# stm32f767igt6.net
KiCad netlist of a schematic drawn in Altium Designer
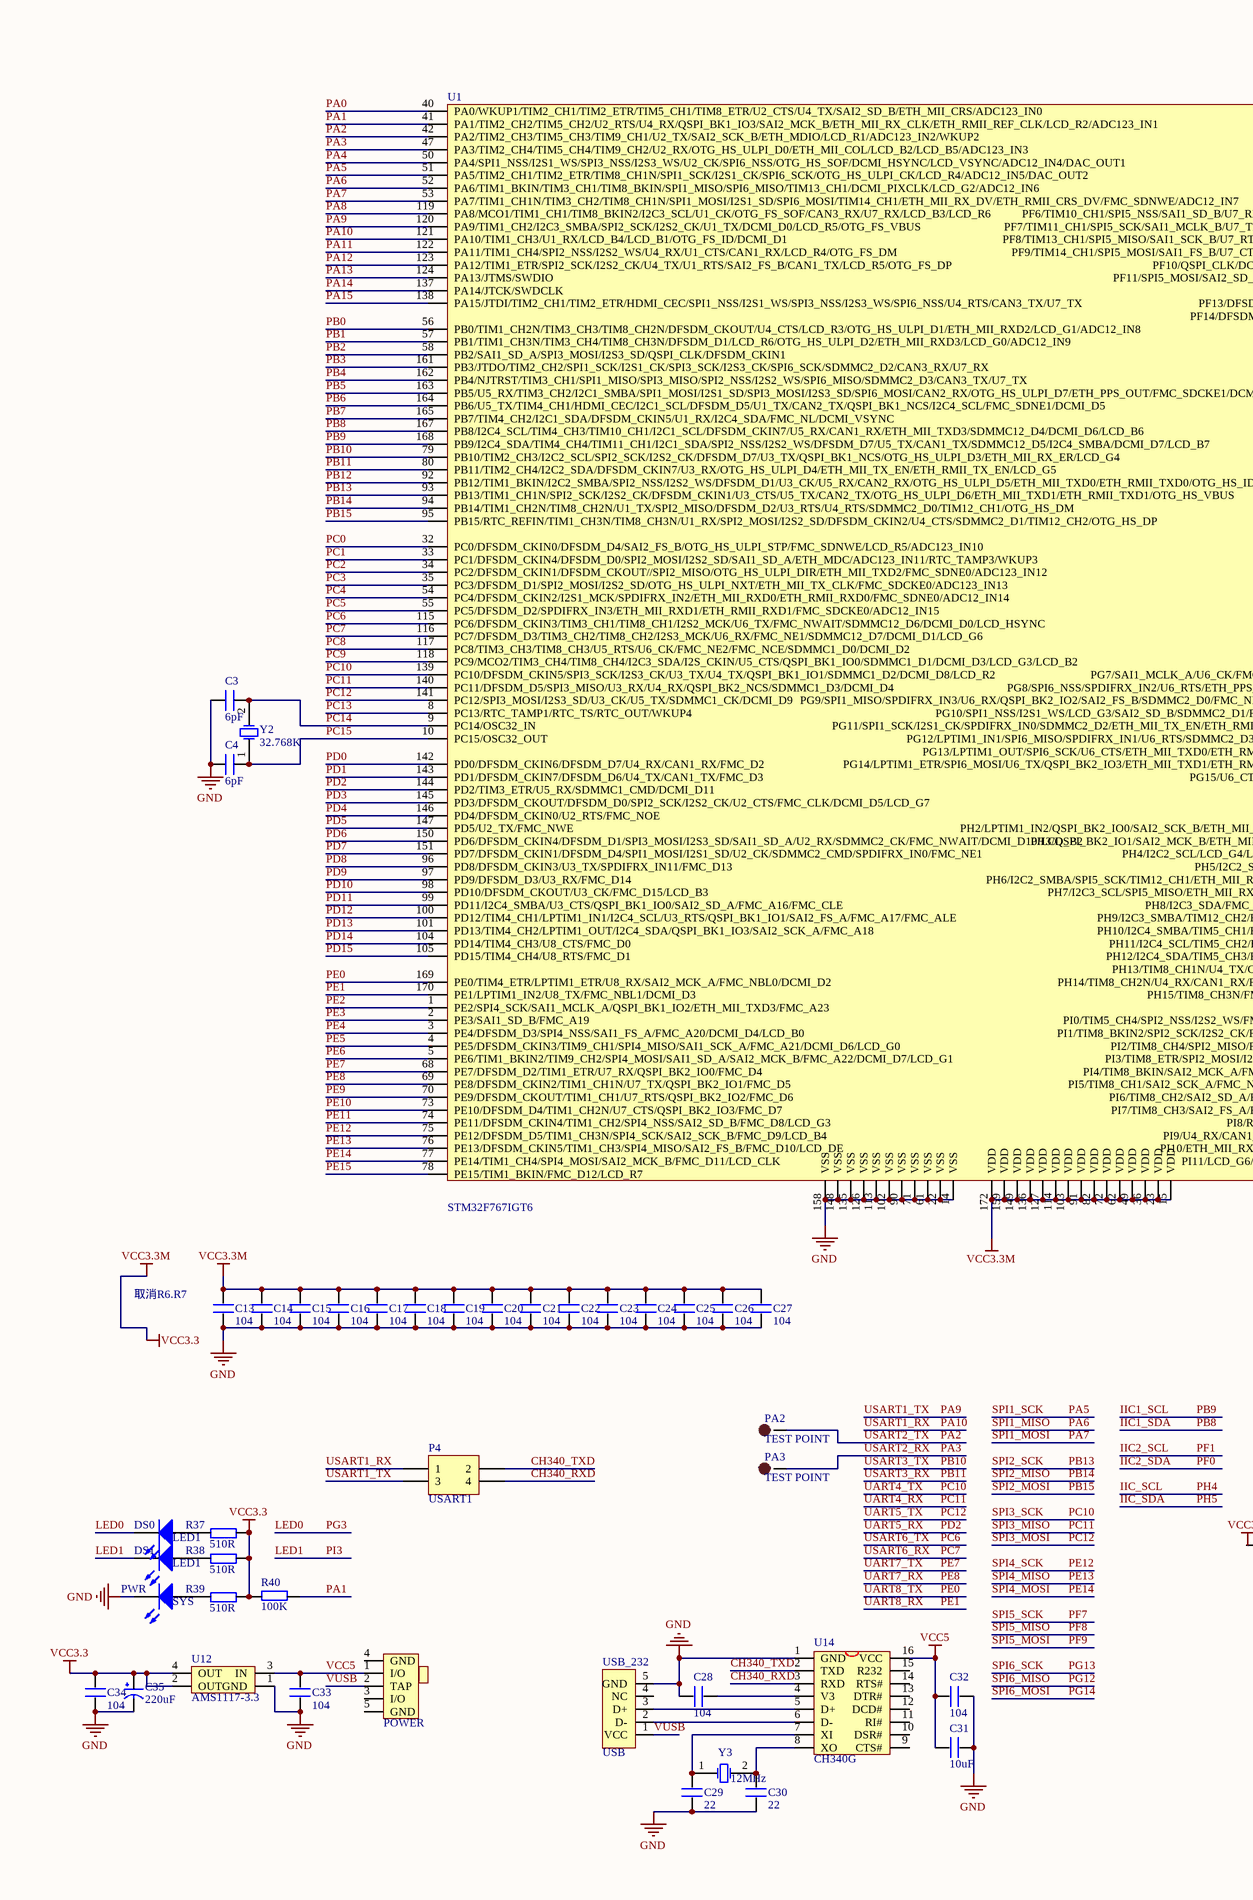
[diagram p0: stm32f767igt6.SchDoc, left]
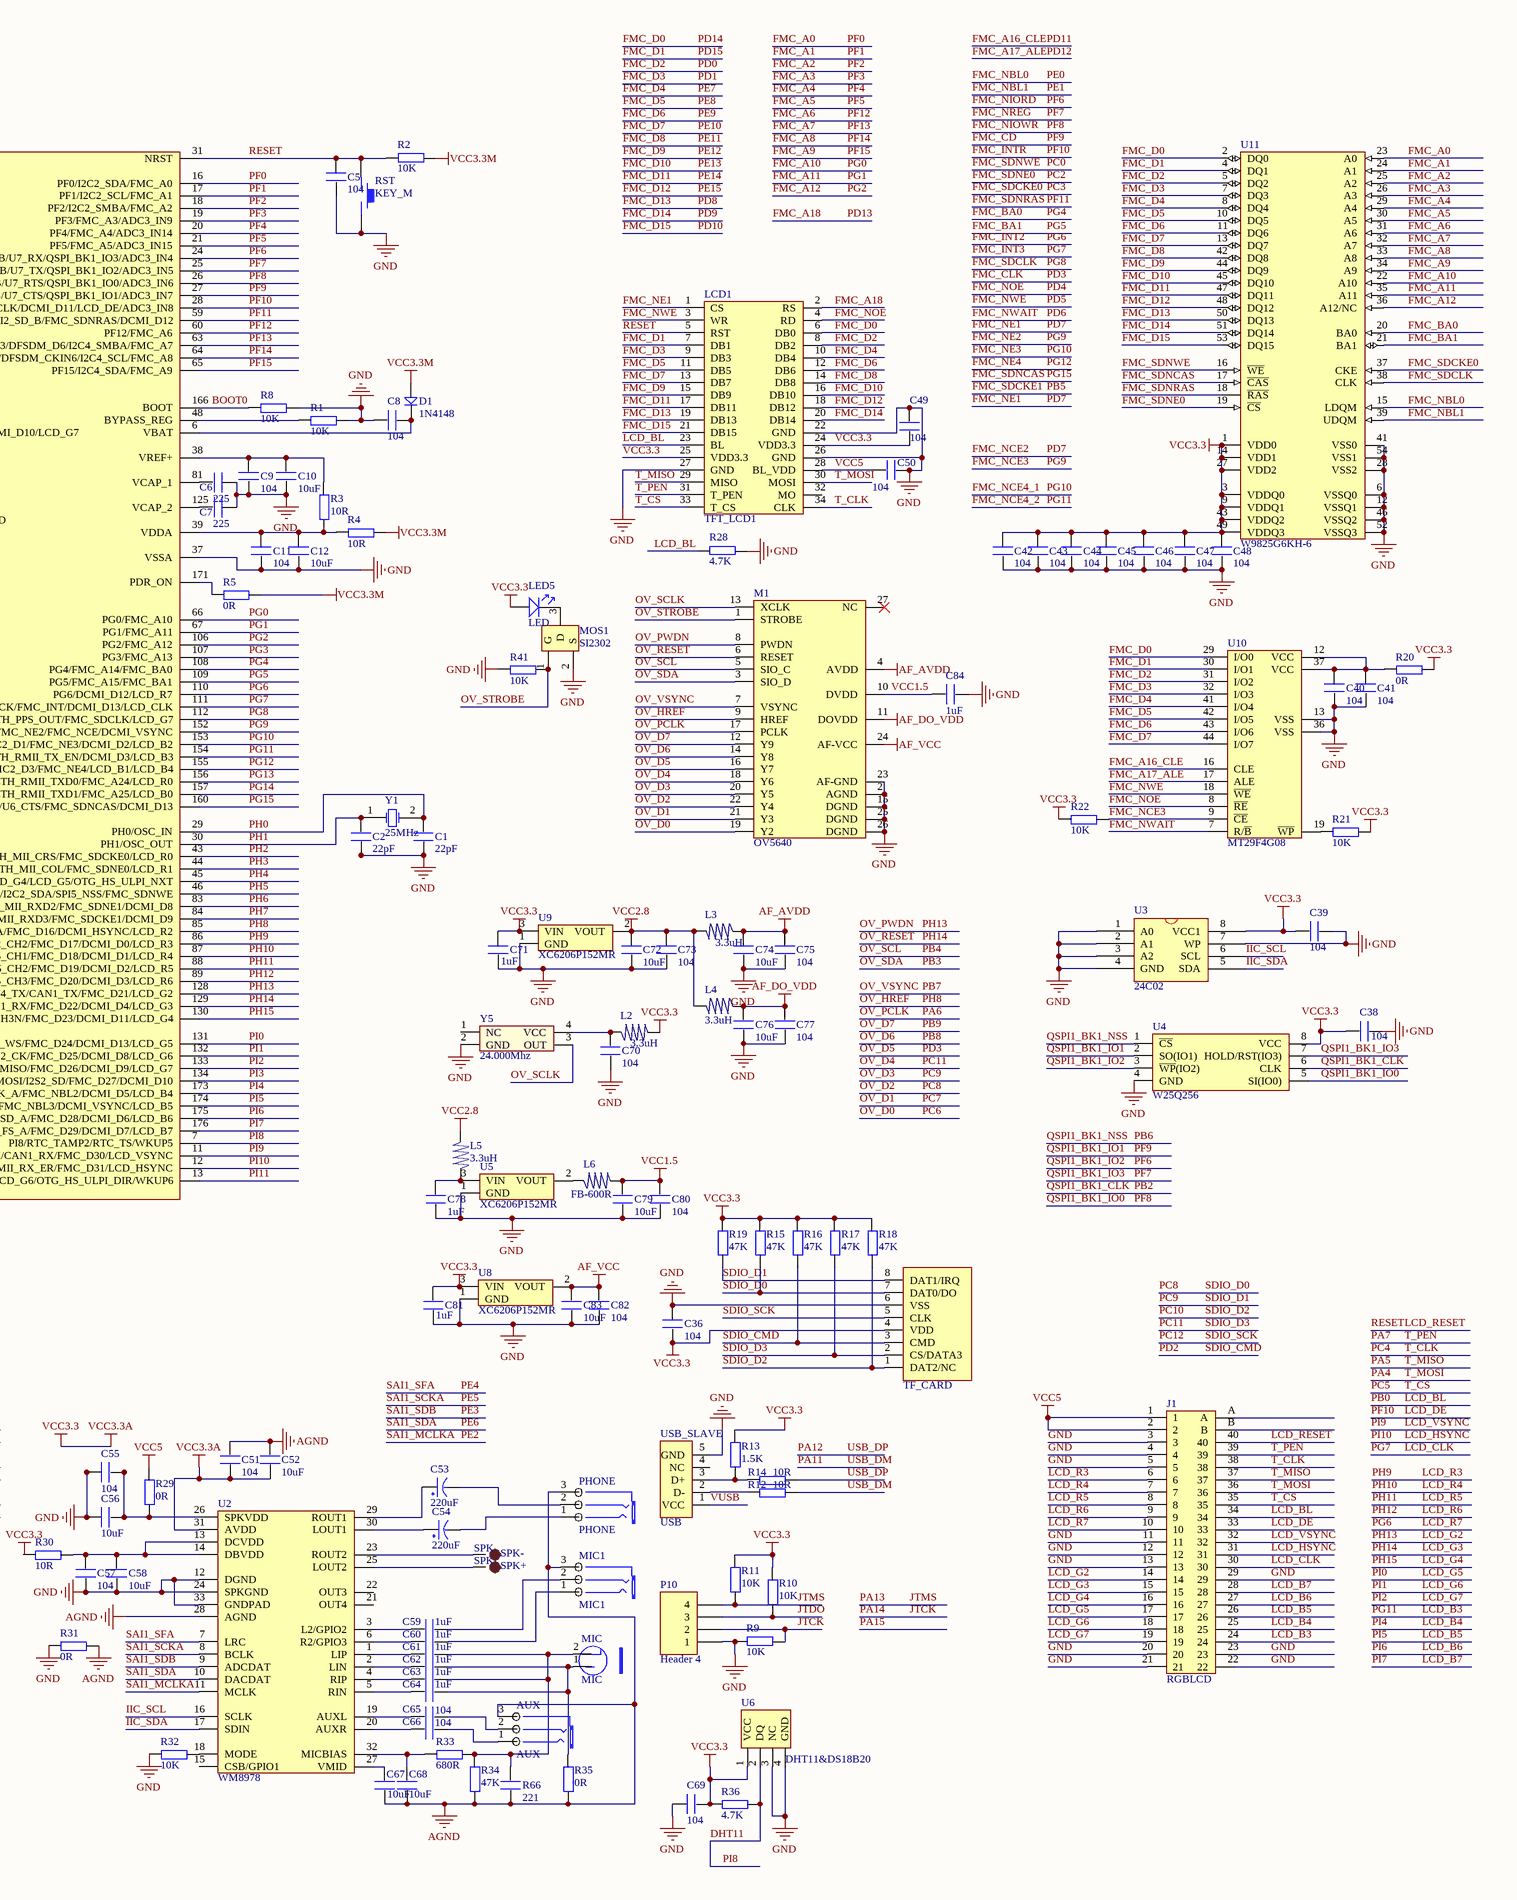
[diagram p1: stm32f767igt6.SchDoc, right]

(export (version "E")
  (design (tool "Eeschema 10.0.6"))
  (components
    (comp (ref "AUX")
      (value "AUX")
      (footprint "PHONE_ST")
      (libsource (lib "阿波罗STM32F4&F7&H7底板封装库") (part "PHONE_M"))
    )
    (comp (ref "C1")
      (value "22pF")
      (footprint "C 0603_M")
      (libsource (lib "WarShip V3 STM32103封装库") (part "C"))
    )
    (comp (ref "C2")
      (value "22pF")
      (footprint "C 0603_M")
      (libsource (lib "WarShip V3 STM32103封装库") (part "C"))
    )
    (comp (ref "C3")
      (value "6pF")
      (footprint "C 0603_M")
      (libsource (lib "WarShip V3 STM32103封装库") (part "C"))
    )
    (comp (ref "C4")
      (value "6pF")
      (footprint "C 0603_M")
      (libsource (lib "WarShip V3 STM32103封装库") (part "C"))
    )
    (comp (ref "C5")
      (value "104")
      (footprint "C 0603_M")
      (libsource (lib "WarShip V3 STM32103封装库") (part "C"))
    )
    (comp (ref "C6") (value "225") (footprint "C 0603_M") (libsource (lib "阿波罗STM32F4&F7底板封装库") (part "C")))
    (comp (ref "C7") (value "225") (footprint "C 0603_M") (libsource (lib "阿波罗STM32F4&F7底板封装库") (part "C")))
    (comp (ref "C8") (value "104") (footprint "C 0603_M") (libsource (lib "阿波罗STM32F4&F7底板封装库") (part "C")))
    (comp (ref "C9") (value "104") (footprint "C 0603_M") (libsource (lib "阿波罗STM32F4&F7底板封装库") (part "C")))
    (comp (ref "C10") (value "10uF") (footprint "C 0603_M") (libsource (lib "阿波罗STM32F4&F7底板封装库") (part "C")))
    (comp (ref "C11") (value "104") (footprint "C 0603_M") (libsource (lib "阿波罗STM32F4&F7底板封装库") (part "C")))
    (comp (ref "C12") (value "10uF") (footprint "C 0603_M") (libsource (lib "阿波罗STM32F4&F7底板封装库") (part "C")))
    (comp (ref "C13") (value "104") (footprint "C 0603_M") (libsource (lib "STM32F429核心板封装库") (part "C")))
    (comp (ref "C14") (value "104") (footprint "C 0603_M") (libsource (lib "STM32F429核心板封装库") (part "C")))
    (comp (ref "C15") (value "104") (footprint "C 0603_M") (libsource (lib "STM32F429核心板封装库") (part "C")))
    (comp (ref "C16") (value "104") (footprint "C 0603_M") (libsource (lib "STM32F429核心板封装库") (part "C")))
    (comp (ref "C17") (value "104") (footprint "C 0603_M") (libsource (lib "STM32F429核心板封装库") (part "C")))
    (comp (ref "C18") (value "104") (footprint "C 0603_M") (libsource (lib "STM32F429核心板封装库") (part "C")))
    (comp (ref "C19") (value "104") (footprint "C 0603_M") (libsource (lib "STM32F429核心板封装库") (part "C")))
    (comp (ref "C20") (value "104") (footprint "C 0603_M") (libsource (lib "STM32F429核心板封装库") (part "C")))
    (comp (ref "C21") (value "104") (footprint "C 0603_M") (libsource (lib "STM32F429核心板封装库") (part "C")))
    (comp (ref "C22") (value "104") (footprint "C 0603_M") (libsource (lib "STM32F429核心板封装库") (part "C")))
    (comp (ref "C23") (value "104") (footprint "C 0603_M") (libsource (lib "STM32F429核心板封装库") (part "C")))
    (comp (ref "C24") (value "104") (footprint "C 0603_M") (libsource (lib "STM32F429核心板封装库") (part "C")))
    (comp (ref "C25") (value "104") (footprint "C 0603_M") (libsource (lib "STM32F429核心板封装库") (part "C")))
    (comp (ref "C26") (value "104") (footprint "C 0603_M") (libsource (lib "STM32F429核心板封装库") (part "C")))
    (comp (ref "C27") (value "104") (footprint "C 0603_M") (libsource (lib "STM32F429核心板封装库") (part "C")))
    (comp (ref "C28")
      (value "104")
      (footprint "C 0603_M")
      (libsource (lib "WarShip V3 STM32103封装库") (part "C"))
    )
    (comp (ref "C29")
      (value "22")
      (footprint "C 0603_M")
      (libsource (lib "WarShip V3 STM32103封装库") (part "C"))
    )
    (comp (ref "C30")
      (value "22")
      (footprint "C 0603_M")
      (libsource (lib "WarShip V3 STM32103封装库") (part "C"))
    )
    (comp (ref "C31")
      (value "10uF")
      (footprint "C 0603_M")
      (libsource (lib "WarShip V3 STM32103封装库") (part "C"))
    )
    (comp (ref "C32")
      (value "104")
      (footprint "C 0603_M")
      (libsource (lib "WarShip V3 STM32103封装库") (part "C"))
    )
    (comp (ref "C33")
      (value "104")
      (footprint "C 0603_M")
      (libsource (lib "WarShip V3 STM32103封装库") (part "C"))
    )
    (comp (ref "C34")
      (value "104")
      (footprint "C 0603_M")
      (libsource (lib "WarShip V3 STM32103封装库") (part "C"))
    )
    (comp (ref "C35")
      (value "220uF")
      (footprint "CT 6*6 - C")
      (libsource (lib "WarShip V3 STM32103封装库") (part "CAP"))
    )
    (comp (ref "C36")
      (value "104")
      (footprint "C 0603_M")
      (libsource (lib "WarShip V3 STM32103封装库") (part "C"))
    )
    (comp (ref "C38")
      (value "104")
      (footprint "C 0603_M")
      (libsource (lib "WarShip V3 STM32103封装库") (part "C"))
    )
    (comp (ref "C39")
      (value "104")
      (footprint "C 0603_M")
      (libsource (lib "WarShip V3 STM32103封装库") (part "C"))
    )
    (comp (ref "C40")
      (value "104")
      (footprint "C 0603_M")
      (libsource (lib "WarShip V3 STM32103封装库") (part "C"))
    )
    (comp (ref "C41")
      (value "104")
      (footprint "C 0603_M")
      (libsource (lib "WarShip V3 STM32103封装库") (part "C"))
    )
    (comp (ref "C42")
      (value "104")
      (footprint "C 0603_M")
      (libsource (lib "WarShip V3 STM32103封装库") (part "C"))
    )
    (comp (ref "C43")
      (value "104")
      (footprint "C 0603_M")
      (libsource (lib "WarShip V3 STM32103封装库") (part "C"))
    )
    (comp (ref "C44")
      (value "104")
      (footprint "C 0603_M")
      (libsource (lib "WarShip V3 STM32103封装库") (part "C"))
    )
    (comp (ref "C45")
      (value "104")
      (footprint "C 0603_M")
      (libsource (lib "WarShip V3 STM32103封装库") (part "C"))
    )
    (comp (ref "C46")
      (value "104")
      (footprint "C 0603_M")
      (libsource (lib "WarShip V3 STM32103封装库") (part "C"))
    )
    (comp (ref "C47")
      (value "104")
      (footprint "C 0603_M")
      (libsource (lib "WarShip V3 STM32103封装库") (part "C"))
    )
    (comp (ref "C48")
      (value "104")
      (footprint "C 0603_M")
      (libsource (lib "WarShip V3 STM32103封装库") (part "C"))
    )
    (comp (ref "C49") (value "104") (footprint "C 0603_M") (libsource (lib "MYCOMLIB") (part "C")))
    (comp (ref "C50") (value "104") (footprint "C 0603_M") (libsource (lib "MYCOMLIB") (part "C")))
    (comp (ref "C51") (value "104") (footprint "C 0603_M") (libsource (lib "阿波罗STM32F4&F7底板封装库") (part "C")))
    (comp (ref "C52") (value "10uF") (footprint "C 0603_M") (libsource (lib "阿波罗STM32F4&F7底板封装库") (part "C")))
    (comp (ref "C53")
      (value "220uF")
      (footprint "cc4*5.4")
      (libsource (lib "阿波罗STM32F4&F7底板封装库") (part "CAP"))
    )
    (comp (ref "C54")
      (value "220uF")
      (footprint "cc4*5.4")
      (libsource (lib "阿波罗STM32F4&F7底板封装库") (part "CAP"))
    )
    (comp (ref "C55") (value "104") (footprint "C 0603_M") (libsource (lib "阿波罗STM32F4&F7底板封装库") (part "C")))
    (comp (ref "C56") (value "10uF") (footprint "C 0603_M") (libsource (lib "阿波罗STM32F4&F7底板封装库") (part "C")))
    (comp (ref "C57") (value "104") (footprint "C 0603_M") (libsource (lib "阿波罗STM32F4&F7底板封装库") (part "C")))
    (comp (ref "C58") (value "10uF") (footprint "C 0603_M") (libsource (lib "阿波罗STM32F4&F7底板封装库") (part "C")))
    (comp (ref "C59") (value "1uF") (footprint "C 0603_M") (libsource (lib "阿波罗STM32F4&F7底板封装库") (part "C")))
    (comp (ref "C60") (value "1uF") (footprint "C 0603_M") (libsource (lib "阿波罗STM32F4&F7底板封装库") (part "C")))
    (comp (ref "C61") (value "1uF") (footprint "C 0603_M") (libsource (lib "阿波罗STM32F4&F7底板封装库") (part "C")))
    (comp (ref "C62") (value "1uF") (footprint "C 0603_M") (libsource (lib "阿波罗STM32F4&F7底板封装库") (part "C")))
    (comp (ref "C63") (value "1uF") (footprint "C 0603_M") (libsource (lib "阿波罗STM32F4&F7底板封装库") (part "C")))
    (comp (ref "C64") (value "1uF") (footprint "C 0603_M") (libsource (lib "阿波罗STM32F4&F7底板封装库") (part "C")))
    (comp (ref "C65") (value "104") (footprint "C 0603_M") (libsource (lib "阿波罗STM32F4&F7底板封装库") (part "C")))
    (comp (ref "C66") (value "104") (footprint "C 0603_M") (libsource (lib "阿波罗STM32F4&F7底板封装库") (part "C")))
    (comp (ref "C67") (value "10uF") (footprint "C 0603_M") (libsource (lib "阿波罗STM32F4&F7底板封装库") (part "C")))
    (comp (ref "C68") (value "10uF") (footprint "C 0603_M") (libsource (lib "阿波罗STM32F4&F7底板封装库") (part "C")))
    (comp (ref "C69")
      (value "104")
      (footprint "C 0603_M")
      (libsource (lib "WarShip V3 STM32103封装库") (part "C"))
    )
    (comp (ref "C70") (value "104") (footprint "C 0603_M") (libsource (lib "ATK-OV5640摄像头模块封装库") (part "C")))
    (comp (ref "C71") (value "1uF") (footprint "C 0603_M") (libsource (lib "ATK-OV5640摄像头模块封装库") (part "C")))
    (comp (ref "C72") (value "10uF") (footprint "C 0603_M") (libsource (lib "ATK-OV5640摄像头模块封装库") (part "C")))
    (comp (ref "C73") (value "104") (footprint "C 0603_M") (libsource (lib "ATK-OV5640摄像头模块封装库") (part "C")))
    (comp (ref "C74") (value "10uF") (footprint "C 0603_M") (libsource (lib "ATK-OV5640摄像头模块封装库") (part "C")))
    (comp (ref "C75") (value "104") (footprint "C 0603_M") (libsource (lib "ATK-OV5640摄像头模块封装库") (part "C")))
    (comp (ref "C76") (value "10uF") (footprint "C 0603_M") (libsource (lib "ATK-OV5640摄像头模块封装库") (part "C")))
    (comp (ref "C77") (value "104") (footprint "C 0603_M") (libsource (lib "ATK-OV5640摄像头模块封装库") (part "C")))
    (comp (ref "C78") (value "1uF") (footprint "C 0603_M") (libsource (lib "ATK-OV5640摄像头模块封装库") (part "C")))
    (comp (ref "C79") (value "10uF") (footprint "C 0603_M") (libsource (lib "ATK-OV5640摄像头模块封装库") (part "C")))
    (comp (ref "C80") (value "104") (footprint "C 0603_M") (libsource (lib "ATK-OV5640摄像头模块封装库") (part "C")))
    (comp (ref "C81") (value "1uF") (footprint "C 0603_M") (libsource (lib "ATK-OV5640摄像头模块封装库") (part "C")))
    (comp (ref "C82") (value "104") (footprint "C 0603_M") (libsource (lib "ATK-OV5640摄像头模块封装库") (part "C")))
    (comp (ref "C83") (value "10uF") (footprint "C 0603_M") (libsource (lib "ATK-OV5640摄像头模块封装库") (part "C")))
    (comp (ref "C84") (value "1uF") (footprint "C 0603_M") (libsource (lib "ATK-OV5640摄像头模块封装库") (part "C")))
    (comp (ref "D1")
      (value "1N4148")
      (footprint "DIODE_SOP")
      (libsource (lib "WarShip V3 STM32103封装库") (part "D"))
    )
    (comp (ref "DS0")
      (value "LED1")
      (footprint "SMDLED")
      (description "Typical RED, GREEN, YELLOW, AMBER GaAs LED")
      (fields (field (name "PUBLISHER") "Altium Limited"))
      (libsource (lib "Miscellaneous Devices") (part "LED2"))
    )
    (comp (ref "DS1")
      (value "LED1")
      (footprint "SMDLED")
      (description "Typical RED, GREEN, YELLOW, AMBER GaAs LED")
      (fields (field (name "PUBLISHER") "Altium Limited"))
      (libsource (lib "Miscellaneous Devices") (part "LED2"))
    )
    (comp (ref "J1")
      (value "RGBLCD")
      (footprint "FPC-TOP40")
      (description "FPC-40P-0.5mm")
      (libsource (lib "STM32F429核心板封装库") (part "FPC-40"))
    )
    (comp (ref "L2") (value "3.3uH") (footprint "L 0603") (libsource (lib "") (part "L_1")))
    (comp (ref "L3") (value "3.3uH") (footprint "L 0603") (libsource (lib "") (part "L_2")))
    (comp (ref "L4") (value "3.3uH") (footprint "L 0603") (libsource (lib "") (part "L_2")))
    (comp (ref "L5") (value "3.3uH") (footprint "L 0603") (libsource (lib "ATK-OV5640摄像头模块封装库") (part "L")))
    (comp (ref "L6") (value "FB-600R") (footprint "L 0603") (libsource (lib "") (part "L_1")))
    (comp (ref "LCD1")
      (value "TFT_LCD1")
      (footprint "HDR2.54-LI-2x17P")
      (libsource (lib "3.5TFTLCD封装库") (part "TFT_LCD2"))
    )
    (comp (ref "LED5")
      (value "LED")
      (footprint "LED 0805R")
      (libsource (lib "ATK-OV5640摄像头模块封装库") (part "LED"))
    )
    (comp (ref "M1")
      (value "OV5640")
      (footprint "OV5640-24")
      (description "OV5640模组,AF,FPC")
      (libsource (lib "ATK-OV5640摄像头模块封装库") (part "OV5640"))
    )
    (comp (ref "MIC")
      (value "MIC")
      (footprint "MIC-6022")
      (libsource (lib "阿波罗STM32F4&F7&H7底板封装库") (part "MIC"))
    )
    (comp (ref "MIC1")
      (value "MIC1")
      (footprint "PHONE_ST")
      (libsource (lib "阿波罗STM32F4&F7&H7底板封装库") (part "PHONE_M"))
    )
    (comp (ref "MOS1")
      (value "SI2302")
      (footprint "SOT23-3M")
      (description "AP2306")
      (libsource (lib "ATK-OV5640摄像头模块封装库") (part "MOS-N"))
    )
    (comp (ref "P4")
      (value "USART1")
      (footprint "HDR2.54-LI-2x2P")
      (description "Header, 2-Pin, Dual row")
      (fields (field (name "PUBLISHER") "Altium Limited"))
      (libsource (lib "WarShip V3 STM32103封装库") (part "Header 2X2"))
    )
    (comp (ref "P10")
      (value "Header 4")
      (footprint "HDR2.54-LI-4P")
      (description "Header, 4-Pin")
      (fields (field (name "PUBLISHER") "Altium Limited"))
      (libsource (lib "WarShip V3 STM32103封装库") (part "Header 4"))
    )
    (comp (ref "PA2")
      (value "TEST POINT")
      (footprint "TP-1.5")
      (description "测试点")
      (libsource (lib "STM32F429核心板封装库") (part "TEST-POINT"))
    )
    (comp (ref "PA3")
      (value "TEST POINT")
      (footprint "TP-1.5")
      (description "测试点")
      (libsource (lib "STM32F429核心板封装库") (part "TEST-POINT"))
    )
    (comp (ref "PHONE")
      (value "PHONE")
      (footprint "PHONE_ST")
      (libsource (lib "阿波罗STM32F4&F7&H7底板封装库") (part "PHONE_M"))
    )
    (comp (ref "POWER")
      (value "BUTTON_DIP3")
      (footprint "BTN8.8*4.6")
      (description "拨动开关SS-12F44")
      (libsource (lib "Pandora_STM32L4_Board_V2.4") (part "BUTTON_DIP3"))
    )
    (comp (ref "PWR")
      (value "SYS")
      (footprint "SMDLED")
      (description "Typical RED, GREEN, YELLOW, AMBER GaAs LED")
      (fields (field (name "PUBLISHER") "Altium Limited"))
      (libsource (lib "Miscellaneous Devices") (part "LED2"))
    )
    (comp (ref "R1") (value "10K") (footprint "R 0603_M") (libsource (lib "阿波罗STM32F4&F7底板封装库") (part "R")))
    (comp (ref "R2")
      (value "10K")
      (footprint "R 0603_M")
      (libsource (lib "WarShip V3 STM32103封装库") (part "R"))
    )
    (comp (ref "R3") (value "10R") (footprint "R 0603_M") (libsource (lib "阿波罗STM32F4&F7底板封装库") (part "R")))
    (comp (ref "R4") (value "10R") (footprint "R 0603_M") (libsource (lib "阿波罗STM32F4&F7底板封装库") (part "R")))
    (comp (ref "R5") (value "0R") (footprint "R 0603_M") (libsource (lib "阿波罗STM32F4&F7底板封装库") (part "R")))
    (comp (ref "R8") (value "10K") (footprint "R 0603_M") (libsource (lib "阿波罗STM32F4&F7底板封装库") (part "R")))
    (comp (ref "R9")
      (value "10K")
      (footprint "R 0603_M")
      (libsource (lib "WarShip V3 STM32103封装库") (part "R"))
    )
    (comp (ref "R10")
      (value "10K")
      (footprint "R 0603_M")
      (libsource (lib "WarShip V3 STM32103封装库") (part "R"))
    )
    (comp (ref "R11")
      (value "10K")
      (footprint "R 0603_M")
      (libsource (lib "WarShip V3 STM32103封装库") (part "R"))
    )
    (comp (ref "R12")
      (value "10R")
      (footprint "R 0603_M")
      (libsource (lib "WarShip V3 STM32103封装库") (part "R"))
    )
    (comp (ref "R13")
      (value "1.5K")
      (footprint "R 0603_M")
      (libsource (lib "WarShip V3 STM32103封装库") (part "R"))
    )
    (comp (ref "R14")
      (value "10R")
      (footprint "R 0603_M")
      (libsource (lib "WarShip V3 STM32103封装库") (part "R"))
    )
    (comp (ref "R15")
      (value "47K")
      (footprint "R 0603_M")
      (libsource (lib "WarShip V3 STM32103封装库") (part "R"))
    )
    (comp (ref "R16")
      (value "47K")
      (footprint "R 0603_M")
      (libsource (lib "WarShip V3 STM32103封装库") (part "R"))
    )
    (comp (ref "R17")
      (value "47K")
      (footprint "R 0603_M")
      (libsource (lib "WarShip V3 STM32103封装库") (part "R"))
    )
    (comp (ref "R18")
      (value "47K")
      (footprint "R 0603_M")
      (libsource (lib "WarShip V3 STM32103封装库") (part "R"))
    )
    (comp (ref "R19")
      (value "47K")
      (footprint "R 0603_M")
      (libsource (lib "WarShip V3 STM32103封装库") (part "R"))
    )
    (comp (ref "R20")
      (value "0R")
      (footprint "R 0603_M")
      (libsource (lib "WarShip V3 STM32103封装库") (part "R"))
    )
    (comp (ref "R21")
      (value "10K")
      (footprint "R 0603_M")
      (libsource (lib "WarShip V3 STM32103封装库") (part "R"))
    )
    (comp (ref "R22")
      (value "10K")
      (footprint "R 0603_M")
      (libsource (lib "WarShip V3 STM32103封装库") (part "R"))
    )
    (comp (ref "R28") (value "4.7K") (footprint "R 0603_M") (libsource (lib "MYCOMLIB") (part "R")))
    (comp (ref "R29") (value "0R") (footprint "R 0603_M") (libsource (lib "阿波罗STM32F4&F7底板封装库") (part "R")))
    (comp (ref "R30") (value "10R") (footprint "R 0603_M") (libsource (lib "阿波罗STM32F4&F7底板封装库") (part "R")))
    (comp (ref "R31") (value "0R") (footprint "R 0603_M") (libsource (lib "阿波罗STM32F4&F7底板封装库") (part "R")))
    (comp (ref "R32") (value "10K") (footprint "R 0603_M") (libsource (lib "阿波罗STM32F4&F7底板封装库") (part "R")))
    (comp (ref "R33") (value "680R") (footprint "R 0603_M") (libsource (lib "阿波罗STM32F4&F7底板封装库") (part "R")))
    (comp (ref "R34") (value "47K") (footprint "R 0603_M") (libsource (lib "阿波罗STM32F4&F7底板封装库") (part "R")))
    (comp (ref "R35") (value "0R") (footprint "R 0603_M") (libsource (lib "阿波罗STM32F4&F7底板封装库") (part "R")))
    (comp (ref "R36")
      (value "4.7K")
      (footprint "R 0603_M")
      (libsource (lib "WarShip V3 STM32103封装库") (part "R"))
    )
    (comp (ref "R37") (value "510R") (footprint "R 0603_M") (libsource (lib "MYCOMLIB") (part "R")))
    (comp (ref "R38") (value "510R") (footprint "R 0603_M") (libsource (lib "MYCOMLIB") (part "R")))
    (comp (ref "R39") (value "510R") (footprint "R 0603_M") (libsource (lib "MYCOMLIB") (part "R")))
    (comp (ref "R40") (value "100K") (footprint "R 0603_M") (libsource (lib "MYCOMLIB") (part "R")))
    (comp (ref "R41") (value "10K") (footprint "R 0603_M") (libsource (lib "ATK-OV5640摄像头模块封装库") (part "R")))
    (comp (ref "R66") (value "221") (footprint "C 0603_M") (libsource (lib "阿波罗STM32F4&F7底板封装库") (part "C")))
    (comp (ref "RST")
      (value "KEY_M")
      (footprint "TSW SMD-3*6*2.5")
      (libsource (lib "STM32F429核心板封装库") (part "KEY_M"))
    )
    (comp (ref "SPK+")
      (value "SPK")
      (footprint "TP-1.5")
      (description "测试点")
      (libsource (lib "STM32F429核心板封装库") (part "TEST-POINT"))
    )
    (comp (ref "SPK-")
      (value "SPK")
      (footprint "TP-1.5")
      (description "测试点")
      (libsource (lib "STM32F429核心板封装库") (part "TEST-POINT"))
    )
    (comp (ref "TF_CARD")
      (value "SD-MICRO-TF")
      (footprint "SD-MICRO-TF")
      (description "SD,MICRO,TF")
      (libsource (lib "Pandora_STM32L4_Board_V2.4") (part "SD-MICRO-TF"))
    )
    (comp (ref "U1")
      (value "STM32F767IGT6")
      (footprint "LQFP176")
      (libsource (lib "STM32F767核心板封装库") (part "STM32F767IGT6"))
    )
    (comp (ref "U2")
      (value "WM8978")
      (footprint "qfn32")
      (description "24bit ADC&DAC")
      (libsource (lib "STM32H743") (part "WM8978"))
    )
    (comp (ref "U3")
      (value "24C02")
      (footprint "SOP8_M")
      (libsource (lib "WarShip V3 STM32103封装库") (part "24C256"))
    )
    (comp (ref "U4")
      (value "W25Q256")
      (footprint "WSON8")
      (description "W25Q128")
      (libsource (lib "STM32F767核心板封装库") (part "W25Q128"))
    )
    (comp (ref "U5")
      (value "XC6206P152MR")
      (footprint "SOT23-3M")
      (description "LDO,SOT23,1.2~5.0V")
      (libsource (lib "ATK-OV5640摄像头模块封装库") (part "XC6206"))
    )
    (comp (ref "U6")
      (value "DHT11&DS18B20")
      (footprint "DHT11")
      (description "数字温湿度传感器")
      (libsource (lib "WarShip V3 STM32103封装库") (part "DHT11"))
    )
    (comp (ref "U8")
      (value "XC6206P152MR")
      (footprint "SOT23-3M")
      (description "LDO,SOT23,1.2~5.0V")
      (libsource (lib "ATK-OV5640摄像头模块封装库") (part "XC6206"))
    )
    (comp (ref "U9")
      (value "XC6206P152MR")
      (footprint "SOT23-3M")
      (description "LDO,SOT23,1.2~5.0V")
      (libsource (lib "ATK-OV5640摄像头模块封装库") (part "XC6206"))
    )
    (comp (ref "U10")
      (value "MT29F4G08")
      (footprint "TSOP48")
      (description "256MB NAND FLASH")
      (libsource (lib "STM32F429核心板封装库") (part "K9F2G08U0C"))
    )
    (comp (ref "U11")
      (value "W9825G6KH-6")
      (footprint "TSOP54")
      (description "32MB SDRAM")
      (libsource (lib "STM32F429核心板封装库") (part "IS42S16160B"))
    )
    (comp (ref "U12")
      (value "AMS1117-3.3")
      (footprint "AMS1117")
      (libsource (lib "WarShip V3 STM32103封装库") (part "AMS1117"))
    )
    (comp (ref "U14")
      (value "CH340G")
      (footprint "SOP16_M")
      (description "USB2UART")
      (libsource (lib "WarShip V3 STM32103封装库") (part "CH340G"))
    )
    (comp (ref "USB_232")
      (value "USB")
      (footprint "USB-MINI-A")
      (libsource (lib "WarShip V3 STM32103封装库") (part "USB5"))
    )
    (comp (ref "USB_SLAVE")
      (value "USB")
      (footprint "USB-MINI-A")
      (libsource (lib "WarShip V3 STM32103封装库") (part "USB5"))
    )
    (comp (ref "Y1")
      (value "25MHz")
      (footprint "OSC HC-49S")
      (description "Crystal Oscillator")
      (fields (field (name "PUBLISHER") "Altium Limited"))
      (libsource (lib "WarShip V3 STM32103封装库") (part "XTAL"))
    )
    (comp (ref "Y2")
      (value "32.768K")
      (footprint "OSC-2x6-WI-A")
      (description "Crystal Oscillator")
      (fields (field (name "PUBLISHER") "Altium Limited"))
      (libsource (lib "WarShip V3 STM32103封装库") (part "XTAL"))
    )
    (comp (ref "Y3")
      (value "12MHz")
      (footprint "OSC HC-49S")
      (description "Crystal Oscillator")
      (fields (field (name "PUBLISHER") "Altium Limited"))
      (libsource (lib "WarShip V3 STM32103封装库") (part "XTAL"))
    )
    (comp (ref "Y5")
      (value "24.000Mhz")
      (footprint "OSC 3225-4P")
      (description "有源晶振")
      (libsource (lib "ATK-OV5640摄像头模块封装库") (part "XTAL_S"))
    )
  )
  (nets
    (net (code "1") (name "/BOOT0") (class "Default")
      (node (ref "R8") (pin "1") (pintype "passive"))
      (node (ref "U1") (pin "166") (pinfunction "BOOT_166") (pintype "passive"))
    )
    (net (code "2") (name "/CH340_RXD") (class "Default")
      (node (ref "P4") (pin "4") (pinfunction "4_4") (pintype "passive"))
      (node (ref "U14") (pin "3") (pinfunction "RXD_3") (pintype "passive"))
    )
    (net (code "3") (name "/CH340_TXD") (class "Default")
      (node (ref "P4") (pin "2") (pinfunction "2_2") (pintype "passive"))
      (node (ref "U14") (pin "2") (pinfunction "TXD_2") (pintype "passive"))
    )
    (net (code "4") (name "/DHT11") (class "Default")
      (node (ref "R36") (pin "2") (pintype "passive"))
      (node (ref "U1") (pin "7") (pinfunction "PI8/RTC_TAMP2/RTC_TS/WKUP5_7") (pintype "passive"))
      (node (ref "U6") (pin "2") (pinfunction "DQ_2") (pintype "passive"))
    )
    (net (code "5") (name "/FMC_A0") (class "Default")
      (node (ref "U1") (pin "16") (pinfunction "PF0/I2C2_SDA/FMC_A0_16") (pintype "passive"))
      (node (ref "U11") (pin "23") (pinfunction "A0_23") (pintype "input"))
    )
    (net (code "6") (name "/FMC_A1") (class "Default")
      (node (ref "U1") (pin "17") (pinfunction "PF1/I2C2_SCL/FMC_A1_17") (pintype "passive"))
      (node (ref "U11") (pin "24") (pinfunction "A1_24") (pintype "input"))
    )
    (net (code "7") (name "/FMC_A2") (class "Default")
      (node (ref "U1") (pin "18") (pinfunction "PF2/I2C2_SMBA/FMC_A2_18") (pintype "passive"))
      (node (ref "U11") (pin "25") (pinfunction "A2_25") (pintype "input"))
    )
    (net (code "8") (name "/FMC_A3") (class "Default")
      (node (ref "U1") (pin "19") (pinfunction "PF3/FMC_A3/ADC3_IN9_19") (pintype "passive"))
      (node (ref "U11") (pin "26") (pinfunction "A3_26") (pintype "input"))
    )
    (net (code "9") (name "/FMC_A4") (class "Default")
      (node (ref "U1") (pin "20") (pinfunction "PF4/FMC_A4/ADC3_IN14_20") (pintype "passive"))
      (node (ref "U11") (pin "29") (pinfunction "A4_29") (pintype "input"))
    )
    (net (code "10") (name "/FMC_A5") (class "Default")
      (node (ref "U1") (pin "21") (pinfunction "PF5/FMC_A5/ADC3_IN15_21") (pintype "passive"))
      (node (ref "U11") (pin "30") (pinfunction "A5_30") (pintype "input"))
    )
    (net (code "11") (name "/FMC_A6") (class "Default")
      (node (ref "U1") (pin "60") (pinfunction "PF12/FMC_A6_60") (pintype "passive"))
      (node (ref "U11") (pin "31") (pinfunction "A6_31") (pintype "input"))
    )
    (net (code "12") (name "/FMC_A7") (class "Default")
      (node (ref "U1") (pin "63") (pinfunction "PF13/DFSDM_D6/I2C4_SMBA/FMC_A7_63") (pintype "passive"))
      (node (ref "U11") (pin "32") (pinfunction "A7_32") (pintype "input"))
    )
    (net (code "13") (name "/FMC_A8") (class "Default")
      (node (ref "U1") (pin "64") (pinfunction "PF14/DFSDM_CKIN6/I2C4_SCL/FMC_A8_64") (pintype "passive"))
      (node (ref "U11") (pin "33") (pinfunction "A8_33") (pintype "input"))
    )
    (net (code "14") (name "/FMC_A9") (class "Default")
      (node (ref "U1") (pin "65") (pinfunction "PF15/I2C4_SDA/FMC_A9_65") (pintype "passive"))
      (node (ref "U11") (pin "34") (pinfunction "A9_34") (pintype "input"))
    )
    (net (code "15") (name "/FMC_A10") (class "Default")
      (node (ref "U1") (pin "66") (pinfunction "PG0/FMC_A10_66") (pintype "passive"))
      (node (ref "U11") (pin "22") (pinfunction "A10_22") (pintype "input"))
    )
    (net (code "16") (name "/FMC_A11") (class "Default")
      (node (ref "U1") (pin "67") (pinfunction "PG1/FMC_A11_67") (pintype "passive"))
      (node (ref "U11") (pin "35") (pinfunction "A11_35") (pintype "input"))
    )
    (net (code "17") (name "/FMC_A12") (class "Default")
      (node (ref "U1") (pin "106") (pinfunction "PG2/FMC_A12_106") (pintype "passive"))
      (node (ref "U11") (pin "36") (pinfunction "A12/NC_36") (pintype "input"))
    )
    (net (code "18") (name "/FMC_A16_CLE") (class "Default")
      (node (ref "U1") (pin "99") (pinfunction "PD11/I2C4_SMBA/U3_CTS/QSPI_BK1_IO0/SAI2_SD_A/FMC_A16/FMC_CLE_99") (pintype "passive"))
      (node (ref "U10") (pin "16") (pinfunction "CLE_16") (pintype "passive"))
    )
    (net (code "19") (name "/FMC_A17_ALE") (class "Default")
      (node (ref "U1") (pin "100") (pinfunction "PD12/TIM4_CH1/LPTIM1_IN1/I2C4_SCL/U3_RTS/QSPI_BK1_IO1/SAI2_FS_A/FMC_A17/FMC_ALE_100") (pintype "passive"))
      (node (ref "U10") (pin "17") (pinfunction "ALE_17") (pintype "passive"))
    )
    (net (code "20") (name "/FMC_A18") (class "Default")
      (node (ref "LCD1") (pin "2") (pinfunction "RS_2") (pintype "passive"))
      (node (ref "U1") (pin "101") (pinfunction "PD13/TIM4_CH2/LPTIM1_OUT/I2C4_SDA/QSPI_BK1_IO3/SAI2_SCK_A/FMC_A18_101") (pintype "passive"))
    )
    (net (code "21") (name "/FMC_BA0") (class "Default")
      (node (ref "U1") (pin "108") (pinfunction "PG4/FMC_A14/FMC_BA0_108") (pintype "passive"))
      (node (ref "U11") (pin "20") (pinfunction "BA0_20") (pintype "input"))
    )
    (net (code "22") (name "/FMC_BA1") (class "Default")
      (node (ref "U1") (pin "109") (pinfunction "PG5/FMC_A15/FMC_BA1_109") (pintype "passive"))
      (node (ref "U11") (pin "21") (pinfunction "BA1_21") (pintype "bidirectional"))
    )
    (net (code "23") (name "/FMC_CD") (class "Default")
      (node (ref "U1") (pin "27") (pinfunction "PF9/TIM14_CH1/SPI5_MOSI/SAI1_FS_B/U7_CTS/QSPI_BK1_IO1/ADC3_IN7_27") (pintype "passive"))
      (node (ref "U4") (pin "2") (pinfunction "SO(IO1)_2") (pintype "passive"))
    )
    (net (code "24") (name "/FMC_CLK") (class "Default")
      (node (ref "M1") (pin "16") (pinfunction "Y7_16") (pintype "passive"))
      (node (ref "U1") (pin "145") (pinfunction "PD3/DFSDM_CKOUT/DFSDM_D0/SPI2_SCK/I2S2_CK/U2_CTS/FMC_CLK/DCMI_D5/LCD_G7_145") (pintype "passive"))
    )
    (net (code "25") (name "/FMC_D0") (class "Default")
      (node (ref "LCD1") (pin "6") (pinfunction "DB0_6") (pintype "passive"))
      (node (ref "U1") (pin "104") (pinfunction "PD14/TIM4_CH3/U8_CTS/FMC_D0_104") (pintype "passive"))
      (node (ref "U10") (pin "29") (pinfunction "I/O0_29") (pintype "passive"))
      (node (ref "U11") (pin "2") (pinfunction "DQ0_2") (pintype "bidirectional"))
    )
    (net (code "26") (name "/FMC_D1") (class "Default")
      (node (ref "LCD1") (pin "7") (pinfunction "DB1_7") (pintype "passive"))
      (node (ref "U1") (pin "105") (pinfunction "PD15/TIM4_CH4/U8_RTS/FMC_D1_105") (pintype "passive"))
      (node (ref "U10") (pin "30") (pinfunction "I/O1_30") (pintype "passive"))
      (node (ref "U11") (pin "4") (pinfunction "DQ1_4") (pintype "bidirectional"))
    )
    (net (code "27") (name "/FMC_D2") (class "Default")
      (node (ref "LCD1") (pin "8") (pinfunction "DB2_8") (pintype "passive"))
      (node (ref "U1") (pin "142") (pinfunction "PD0/DFSDM_CKIN6/DFSDM_D7/U4_RX/CAN1_RX/FMC_D2_142") (pintype "passive"))
      (node (ref "U10") (pin "31") (pinfunction "I/O2_31") (pintype "passive"))
      (node (ref "U11") (pin "5") (pinfunction "DQ2_5") (pintype "bidirectional"))
    )
    (net (code "28") (name "/FMC_D3") (class "Default")
      (node (ref "LCD1") (pin "9") (pinfunction "DB3_9") (pintype "passive"))
      (node (ref "U1") (pin "143") (pinfunction "PD1/DFSDM_CKIN7/DFSDM_D6/U4_TX/CAN1_TX/FMC_D3_143") (pintype "passive"))
      (node (ref "U10") (pin "32") (pinfunction "I/O3_32") (pintype "passive"))
      (node (ref "U11") (pin "7") (pinfunction "DQ3_7") (pintype "bidirectional"))
    )
    (net (code "29") (name "/FMC_D4") (class "Default")
      (node (ref "LCD1") (pin "10") (pinfunction "DB4_10") (pintype "passive"))
      (node (ref "U1") (pin "68") (pinfunction "PE7/DFSDM_D2/TIM1_ETR/U7_RX/QSPI_BK2_IO0/FMC_D4_68") (pintype "passive"))
      (node (ref "U10") (pin "41") (pinfunction "I/O4_41") (pintype "passive"))
      (node (ref "U11") (pin "8") (pinfunction "DQ4_8") (pintype "bidirectional"))
    )
    (net (code "30") (name "/FMC_D5") (class "Default")
      (node (ref "LCD1") (pin "11") (pinfunction "DB5_11") (pintype "passive"))
      (node (ref "U1") (pin "69") (pinfunction "PE8/DFSDM_CKIN2/TIM1_CH1N/U7_TX/QSPI_BK2_IO1/FMC_D5_69") (pintype "passive"))
      (node (ref "U10") (pin "42") (pinfunction "I/O5_42") (pintype "passive"))
      (node (ref "U11") (pin "10") (pinfunction "DQ5_10") (pintype "bidirectional"))
    )
    (net (code "31") (name "/FMC_D6") (class "Default")
      (node (ref "LCD1") (pin "12") (pinfunction "DB6_12") (pintype "passive"))
      (node (ref "U1") (pin "70") (pinfunction "PE9/DFSDM_CKOUT/TIM1_CH1/U7_RTS/QSPI_BK2_IO2/FMC_D6_70") (pintype "passive"))
      (node (ref "U10") (pin "43") (pinfunction "I/O6_43") (pintype "passive"))
      (node (ref "U11") (pin "11") (pinfunction "DQ6_11") (pintype "bidirectional"))
    )
    (net (code "32") (name "/FMC_D7") (class "Default")
      (node (ref "LCD1") (pin "13") (pinfunction "DB7_13") (pintype "passive"))
      (node (ref "U1") (pin "73") (pinfunction "PE10/DFSDM_D4/TIM1_CH2N/U7_CTS/QSPI_BK2_IO3/FMC_D7_73") (pintype "passive"))
      (node (ref "U10") (pin "44") (pinfunction "I/O7_44") (pintype "passive"))
      (node (ref "U11") (pin "13") (pinfunction "DQ7_13") (pintype "bidirectional"))
    )
    (net (code "33") (name "/FMC_D8") (class "Default")
      (node (ref "LCD1") (pin "14") (pinfunction "DB8_14") (pintype "passive"))
      (node (ref "U1") (pin "74") (pinfunction "PE11/DFSDM_CKIN4/TIM1_CH2/SPI4_NSS/SAI2_SD_B/FMC_D8/LCD_G3_74") (pintype "passive"))
      (node (ref "U11") (pin "42") (pinfunction "DQ8_42") (pintype "bidirectional"))
    )
    (net (code "34") (name "/FMC_D9") (class "Default")
      (node (ref "LCD1") (pin "15") (pinfunction "DB9_15") (pintype "passive"))
      (node (ref "U1") (pin "75") (pinfunction "PE12/DFSDM_D5/TIM1_CH3N/SPI4_SCK/SAI2_SCK_B/FMC_D9/LCD_B4_75") (pintype "passive"))
      (node (ref "U11") (pin "44") (pinfunction "DQ9_44") (pintype "bidirectional"))
    )
    (net (code "35") (name "/FMC_D10") (class "Default")
      (node (ref "LCD1") (pin "16") (pinfunction "DB10_16") (pintype "passive"))
      (node (ref "U1") (pin "76") (pinfunction "PE13/DFSDM_CKIN5/TIM1_CH3/SPI4_MISO/SAI2_FS_B/FMC_D10/LCD_DE_76") (pintype "passive"))
      (node (ref "U11") (pin "45") (pinfunction "DQ10_45") (pintype "bidirectional"))
    )
    (net (code "36") (name "/FMC_D11") (class "Default")
      (node (ref "LCD1") (pin "17") (pinfunction "DB11_17") (pintype "passive"))
      (node (ref "U1") (pin "77") (pinfunction "PE14/TIM1_CH4/SPI4_MOSI/SAI2_MCK_B/FMC_D11/LCD_CLK_77") (pintype "passive"))
      (node (ref "U11") (pin "47") (pinfunction "DQ11_47") (pintype "bidirectional"))
    )
    (net (code "37") (name "/FMC_D12") (class "Default")
      (node (ref "LCD1") (pin "18") (pinfunction "DB12_18") (pintype "passive"))
      (node (ref "U1") (pin "78") (pinfunction "PE15/TIM1_BKIN/FMC_D12/LCD_R7_78") (pintype "passive"))
      (node (ref "U11") (pin "48") (pinfunction "DQ12_48") (pintype "bidirectional"))
    )
    (net (code "38") (name "/FMC_D13") (class "Default")
      (node (ref "LCD1") (pin "19") (pinfunction "DB13_19") (pintype "passive"))
      (node (ref "U1") (pin "96") (pinfunction "PD8/DFSDM_CKIN3/U3_TX/SPDIFRX_IN11/FMC_D13_96") (pintype "passive"))
      (node (ref "U11") (pin "50") (pinfunction "DQ13_50") (pintype "bidirectional"))
    )
    (net (code "39") (name "/FMC_D14") (class "Default")
      (node (ref "LCD1") (pin "20") (pinfunction "DB14_20") (pintype "passive"))
      (node (ref "U1") (pin "97") (pinfunction "PD9/DFSDM_D3/U3_RX/FMC_D14_97") (pintype "passive"))
      (node (ref "U11") (pin "51") (pinfunction "DQ14_51") (pintype "bidirectional"))
    )
    (net (code "40") (name "/FMC_D15") (class "Default")
      (node (ref "LCD1") (pin "21") (pinfunction "DB15_21") (pintype "passive"))
      (node (ref "U1") (pin "98") (pinfunction "PD10/DFSDM_CKOUT/U3_CK/FMC_D15/LCD_B3_98") (pintype "passive"))
      (node (ref "U11") (pin "53") (pinfunction "DQ15_53") (pintype "bidirectional"))
    )
    (net (code "41") (name "/FMC_INT2") (class "Default")
      (node (ref "J1") (pin "10") (pinfunction "10_10") (pintype "passive"))
      (node (ref "U1") (pin "110") (pinfunction "PG6/DCMI_D12/LCD_R7_110") (pintype "passive"))
    )
    (net (code "42") (name "/FMC_INT3") (class "Default")
      (node (ref "J1") (pin "30") (pinfunction "30_30") (pintype "passive"))
      (node (ref "U1") (pin "111") (pinfunction "PG7/SAI1_MCLK_A/U6_CK/FMC_INT/DCMI_D13/LCD_CLK_111") (pintype "passive"))
    )
    (net (code "43") (name "/FMC_INTR") (class "Default")
      (node (ref "J1") (pin "33") (pinfunction "33_33") (pintype "passive"))
      (node (ref "U1") (pin "28") (pinfunction "PF10/QSPI_CLK/DCMI_D11/LCD_DE/ADC3_IN8_28") (pintype "passive"))
    )
    (net (code "44") (name "/FMC_NBL0") (class "Default")
      (node (ref "U1") (pin "169") (pinfunction "PE0/TIM4_ETR/LPTIM1_ETR/U8_RX/SAI2_MCK_A/FMC_NBL0/DCMI_D2_169") (pintype "passive"))
      (node (ref "U11") (pin "15") (pinfunction "LDQM_15") (pintype "input"))
    )
    (net (code "45") (name "/FMC_NBL1") (class "Default")
      (node (ref "U1") (pin "170") (pinfunction "PE1/LPTIM1_IN2/U8_TX/FMC_NBL1/DCMI_D3_170") (pintype "passive"))
      (node (ref "U11") (pin "39") (pinfunction "UDQM_39") (pintype "input"))
    )
    (net (code "46") (name "/FMC_NCE2") (class "Default")
      (node (ref "LCD1") (pin "1") (pinfunction "CS_1") (pintype "passive"))
      (node (ref "U1") (pin "151") (pinfunction "PD7/DFSDM_CKIN1/DFSDM_D4/SPI1_MOSI/I2S1_SD/U2_CK/SDMMC2_CMD/SPDIFRX_IN0/FMC_NE1_151") (pintype "passive"))
    )
    (net (code "47") (name "/FMC_NCE3") (class "Default")
      (node (ref "R22") (pin "2") (pintype "passive"))
      (node (ref "U1") (pin "152") (pinfunction "PG9/SPI1_MISO/SPDIFRX_IN3/U6_RX/QSPI_BK2_IO2/SAI2_FS_B/SDMMC2_D0/FMC_NE2/FMC_NCE/DCMI_VSYNC_152") (pintype "passive"))
      (node (ref "U10") (pin "9") (pinfunction "~{CE}_9") (pintype "passive"))
    )
    (net (code "48") (name "/FMC_NCE4_1") (class "Default")
      (node (ref "U1") (pin "153") (pinfunction "PG10/SPI1_NSS/I2S1_WS/LCD_G3/SAI2_SD_B/SDMMC2_D1/FMC_NE3/DCMI_D2/LCD_B2_153") (pintype "passive"))
    )
    (net (code "49") (name "/FMC_NCE4_2") (class "Default")
      (node (ref "J1") (pin "24") (pinfunction "24_24") (pintype "passive"))
      (node (ref "U1") (pin "154") (pinfunction "PG11/SPI1_SCK/I2S1_CK/SPDIFRX_IN0/SDMMC2_D2/ETH_MII_TX_EN/ETH_RMII_TX_EN/DCMI_D3/LCD_B3_154") (pintype "passive"))
    )
    (net (code "50") (name "/FMC_NE4") (class "Default")
      (node (ref "U1") (pin "155") (pinfunction "PG12/LPTIM1_IN1/SPI6_MISO/SPDIFRX_IN1/U6_RTS/SDMMC2_D3/FMC_NE4/LCD_B1/LCD_B4_155") (pintype "passive"))
    )
    (net (code "51") (name "/FMC_NIORD") (class "Default")
      (node (ref "U1") (pin "24") (pinfunction "PF6/TIM10_CH1/SPI5_NSS/SAI1_SD_B/U7_RX/QSPI_BK1_IO3/ADC3_IN4_24") (pintype "passive"))
      (node (ref "U4") (pin "3") (pinfunction "~{WP}(IO2)_3") (pintype "passive"))
    )
    (net (code "52") (name "/FMC_NIOWR") (class "Default")
      (node (ref "U1") (pin "26") (pinfunction "PF8/TIM13_CH1/SPI5_MISO/SAI1_SCK_B/U7_RTS/QSPI_BK1_IO0/ADC3_IN6_26") (pintype "passive"))
      (node (ref "U4") (pin "5") (pinfunction "SI(IO0)_5") (pintype "power_in"))
    )
    (net (code "53") (name "/FMC_NOE") (class "Default")
      (node (ref "LCD1") (pin "4") (pinfunction "RD_4") (pintype "passive"))
      (node (ref "U1") (pin "146") (pinfunction "PD4/DFSDM_CKIN0/U2_RTS/FMC_NOE_146") (pintype "passive"))
      (node (ref "U10") (pin "8") (pinfunction "~{RE}_8") (pintype "passive"))
    )
    (net (code "54") (name "/FMC_NREG") (class "Default")
      (node (ref "U1") (pin "25") (pinfunction "PF7/TIM11_CH1/SPI5_SCK/SAI1_MCLK_B/U7_TX/QSPI_BK1_IO2/ADC3_IN5_25") (pintype "passive"))
      (node (ref "U4") (pin "7") (pinfunction "HOLD/RST(IO3)_7") (pintype "power_in"))
    )
    (net (code "55") (name "/FMC_NWAIT") (class "Default")
      (node (ref "U1") (pin "150") (pinfunction "PD6/DFSDM_CKIN4/DFSDM_D1/SPI3_MOSI/I2S3_SD/SAI1_SD_A/U2_RX/SDMMC2_CK/FMC_NWAIT/DCMI_D10/LCD_B2_150") (pintype "passive"))
      (node (ref "U10") (pin "7") (pinfunction "R/~{B}_7") (pintype "passive"))
    )
    (net (code "56") (name "/FMC_NWE") (class "Default")
      (node (ref "LCD1") (pin "3") (pinfunction "WR_3") (pintype "passive"))
      (node (ref "U1") (pin "147") (pinfunction "PD5/U2_TX/FMC_NWE_147") (pintype "passive"))
      (node (ref "U10") (pin "18") (pinfunction "~{WE}_18") (pintype "passive"))
    )
    (net (code "57") (name "/FMC_SDCKE0") (class "Default")
      (node (ref "U1") (pin "35") (pinfunction "PC3/DFSDM_D1/SPI2_MOSI/I2S2_SD/OTG_HS_ULPI_NXT/ETH_MII_TX_CLK/FMC_SDCKE0/ADC123_IN13_35") (pintype "passive"))
      (node (ref "U11") (pin "37") (pinfunction "CKE_37") (pintype "input"))
    )
    (net (code "58") (name "/FMC_SDCKE1") (class "Default")
      (node (ref "U1") (pin "163") (pinfunction "PB5/U5_RX/TIM3_CH2/I2C1_SMBA/SPI1_MOSI/I2S1_SD/SPI3_MOSI/I2S3_SD/SPI6_MOSI/CAN2_RX/OTG_HS_ULPI_D7/ETH_PPS_OUT/FMC_SDCKE1/DCMI_D10/LCD_G7_163") (pintype "passive"))
    )
    (net (code "59") (name "/FMC_SDCLK") (class "Default")
      (node (ref "U1") (pin "112") (pinfunction "PG8/SPI6_NSS/SPDIFRX_IN2/U6_RTS/ETH_PPS_OUT/FMC_SDCLK/LCD_G7_112") (pintype "passive"))
      (node (ref "U11") (pin "38") (pinfunction "CLK_38") (pintype "input"))
    )
    (net (code "60") (name "/FMC_SDNCAS") (class "Default")
      (node (ref "U1") (pin "160") (pinfunction "PG15/U6_CTS/FMC_SDNCAS/DCMI_D13_160") (pintype "passive"))
      (node (ref "U11") (pin "17") (pinfunction "~{CAS}_17") (pintype "input"))
    )
    (net (code "61") (name "/FMC_SDNE0") (class "Default")
      (node (ref "U1") (pin "34") (pinfunction "PC2/DFSDM_CKIN1/DFSDM_CKOUT//SPI2_MISO/OTG_HS_ULPI_DIR/ETH_MII_TXD2/FMC_SDNE0/ADC123_IN12_34") (pintype "passive"))
      (node (ref "U11") (pin "19") (pinfunction "~{CS}_19") (pintype "input"))
    )
    (net (code "62") (name "/FMC_SDNRAS") (class "Default")
      (node (ref "U1") (pin "59") (pinfunction "PF11/SPI5_MOSI/SAI2_SD_B/FMC_SDNRAS/DCMI_D12_59") (pintype "passive"))
      (node (ref "U11") (pin "18") (pinfunction "~{RAS}_18") (pintype "passive"))
    )
    (net (code "63") (name "/FMC_SDNWE") (class "Default")
      (node (ref "U1") (pin "32") (pinfunction "PC0/DFSDM_CKIN0/DFSDM_D4/SAI2_FS_B/OTG_HS_ULPI_STP/FMC_SDNWE/LCD_R5/ADC123_IN10_32") (pintype "passive"))
      (node (ref "U11") (pin "16") (pinfunction "~{WE}_16") (pintype "input"))
    )
    (net (code "64") (name "/IIC1_SCL") (class "Default")
      (node (ref "M1") (pin "12") (pinfunction "Y9_12") (pintype "passive"))
      (node (ref "U1") (pin "168") (pinfunction "PB9/I2C4_SDA/TIM4_CH4/TIM11_CH1/I2C1_SDA/SPI2_NSS/I2S2_WS/DFSDM_D7/U5_TX/CAN1_TX/SDMMC12_D5/I2C4_SMBA/DCMI_D7/LCD_B7_168") (pintype "passive"))
    )
    (net (code "65") (name "/IIC1_SDA") (class "Default")
      (node (ref "M1") (pin "14") (pinfunction "Y8_14") (pintype "passive"))
      (node (ref "U1") (pin "167") (pinfunction "PB8/I2C4_SCL/TIM4_CH3/TIM10_CH1/I2C1_SCL/DFSDM_CKIN7/U5_RX/CAN1_RX/ETH_MII_TXD3/SDMMC12_D4/DCMI_D6/LCD_B6_167") (pintype "passive"))
    )
    (net (code "66") (name "/IIC_SCL") (class "Default")
      (node (ref "U1") (pin "45") (pinfunction "PH4/I2C2_SCL/LCD_G4/LCD_G5/OTG_HS_ULPI_NXT_45") (pintype "passive"))
      (node (ref "U2") (pin "16") (pinfunction "SCLK_16") (pintype "passive"))
      (node (ref "U3") (pin "6") (pinfunction "SCL_6") (pintype "passive"))
    )
    (net (code "67") (name "/IIC_SDA") (class "Default")
      (node (ref "U1") (pin "46") (pinfunction "PH5/I2C2_SDA/SPI5_NSS/FMC_SDNWE_46") (pintype "passive"))
      (node (ref "U2") (pin "17") (pinfunction "SDIN_17") (pintype "passive"))
      (node (ref "U3") (pin "5") (pinfunction "SDA_5") (pintype "passive"))
    )
    (net (code "68") (name "/JTCK") (class "Default")
      (node (ref "P10") (pin "2") (pinfunction "2_2") (pintype "passive"))
      (node (ref "R9") (pin "1") (pintype "passive"))
      (node (ref "U1") (pin "137") (pinfunction "PA14/JTCK/SWDCLK_137") (pintype "passive"))
    )
    (net (code "69") (name "/JTDO") (class "Default")
      (node (ref "P10") (pin "3") (pinfunction "3_3") (pintype "passive"))
      (node (ref "R10") (pin "1") (pintype "passive"))
    )
    (net (code "70") (name "/JTMS") (class "Default")
      (node (ref "P10") (pin "4") (pinfunction "4_4") (pintype "passive"))
      (node (ref "R11") (pin "1") (pintype "passive"))
      (node (ref "U1") (pin "124") (pinfunction "PA13/JTMS/SWDIO_124") (pintype "passive"))
    )
    (net (code "71") (name "/LCD_B4") (class "Default")
      (node (ref "J1") (pin "25") (pinfunction "25_25") (pintype "passive"))
      (node (ref "U1") (pin "173") (pinfunction "PI4/TIM8_BKIN/SAI2_MCK_A/FMC_NBL2/DCMI_D5/LCD_B4_173") (pintype "passive"))
    )
    (net (code "72") (name "/LCD_B5") (class "Default")
      (node (ref "J1") (pin "26") (pinfunction "26_26") (pintype "passive"))
      (node (ref "U1") (pin "174") (pinfunction "PI5/TIM8_CH1/SAI2_SCK_A/FMC_NBL3/DCMI_VSYNC/LCD_B5_174") (pintype "passive"))
    )
    (net (code "73") (name "/LCD_B6") (class "Default")
      (node (ref "J1") (pin "27") (pinfunction "27_27") (pintype "passive"))
      (node (ref "U1") (pin "175") (pinfunction "PI6/TIM8_CH2/SAI2_SD_A/FMC_D28/DCMI_D6/LCD_B6_175") (pintype "passive"))
    )
    (net (code "74") (name "/LCD_B7") (class "Default")
      (node (ref "J1") (pin "28") (pinfunction "28_28") (pintype "passive"))
      (node (ref "U1") (pin "176") (pinfunction "PI7/TIM8_CH3/SAI2_FS_A/FMC_D29/DCMI_D7/LCD_B7_176") (pintype "passive"))
    )
    (net (code "75") (name "/LCD_BL") (class "Default")
      (node (ref "J1") (pin "34") (pinfunction "34_34") (pintype "passive"))
      (node (ref "LCD1") (pin "23") (pinfunction "BL_23") (pintype "passive"))
      (node (ref "R28") (pin "2") (pintype "passive"))
      (node (ref "U1") (pin "56") (pinfunction "PB0/TIM1_CH2N/TIM3_CH3/TIM8_CH2N/DFSDM_CKOUT/U4_CTS/LCD_R3/OTG_HS_ULPI_D1/ETH_MII_RXD2/LCD_G1/ADC12_IN8_56") (pintype "passive"))
    )
    (net (code "76") (name "/LCD_G2") (class "Default")
      (node (ref "J1") (pin "14") (pinfunction "14_14") (pintype "passive"))
      (node (ref "M1") (pin "8") (pinfunction "PWDN_8") (pintype "passive"))
      (node (ref "U1") (pin "128") (pinfunction "PH13/TIM8_CH1N/U4_TX/CAN1_TX/FMC_D21/LCD_G2_128") (pintype "passive"))
    )
    (net (code "77") (name "/LCD_G3") (class "Default")
      (node (ref "J1") (pin "15") (pinfunction "15_15") (pintype "passive"))
      (node (ref "M1") (pin "6") (pinfunction "RESET_6") (pintype "passive"))
      (node (ref "U1") (pin "129") (pinfunction "PH14/TIM8_CH2N/U4_RX/CAN1_RX/FMC_D22/DCMI_D4/LCD_G3_129") (pintype "passive"))
    )
    (net (code "78") (name "/LCD_G4") (class "Default")
      (node (ref "J1") (pin "16") (pinfunction "16_16") (pintype "passive"))
      (node (ref "U1") (pin "130") (pinfunction "PH15/TIM8_CH3N/FMC_D23/DCMI_D11/LCD_G4_130") (pintype "passive"))
    )
    (net (code "79") (name "/LCD_G5") (class "Default")
      (node (ref "J1") (pin "17") (pinfunction "17_17") (pintype "passive"))
      (node (ref "U1") (pin "131") (pinfunction "PI0/TIM5_CH4/SPI2_NSS/I2S2_WS/FMC_D24/DCMI_D13/LCD_G5_131") (pintype "passive"))
    )
    (net (code "80") (name "/LCD_G6") (class "Default")
      (node (ref "J1") (pin "18") (pinfunction "18_18") (pintype "passive"))
      (node (ref "U1") (pin "132") (pinfunction "PI1/TIM8_BKIN2/SPI2_SCK/I2S2_CK/FMC_D25/DCMI_D8/LCD_G6_132") (pintype "passive"))
    )
    (net (code "81") (name "/LCD_G7") (class "Default")
      (node (ref "J1") (pin "19") (pinfunction "19_19") (pintype "passive"))
      (node (ref "U1") (pin "133") (pinfunction "PI2/TIM8_CH4/SPI2_MISO/FMC_D26/DCMI_D9/LCD_G7_133") (pintype "passive"))
    )
    (net (code "82") (name "/LCD_HSYNC") (class "Default")
      (node (ref "J1") (pin "31") (pinfunction "31_31") (pintype "passive"))
      (node (ref "U1") (pin "12") (pinfunction "PI10/ETH_MII_RX_ER/FMC_D31/LCD_HSYNC_12") (pintype "passive"))
    )
    (net (code "83") (name "/LCD_R3") (class "Default")
      (node (ref "J1") (pin "6") (pinfunction "6_6") (pintype "passive"))
      (node (ref "U1") (pin "86") (pinfunction "PH9/I2C3_SMBA/TIM12_CH2/FMC_D17/DCMI_D0/LCD_R3_86") (pintype "passive"))
    )
    (net (code "84") (name "/LCD_R4") (class "Default")
      (node (ref "J1") (pin "7") (pinfunction "7_7") (pintype "passive"))
      (node (ref "U1") (pin "87") (pinfunction "PH10/I2C4_SMBA/TIM5_CH1/FMC_D18/DCMI_D1/LCD_R4_87") (pintype "passive"))
    )
    (net (code "85") (name "/LCD_R5") (class "Default")
      (node (ref "J1") (pin "8") (pinfunction "8_8") (pintype "passive"))
      (node (ref "U1") (pin "88") (pinfunction "PH11/I2C4_SCL/TIM5_CH2/FMC_D19/DCMI_D2/LCD_R5_88") (pintype "passive"))
    )
    (net (code "86") (name "/LCD_R6") (class "Default")
      (node (ref "J1") (pin "9") (pinfunction "9_9") (pintype "passive"))
      (node (ref "U1") (pin "89") (pinfunction "PH12/I2C4_SDA/TIM5_CH3/FMC_D20/DCMI_D3/LCD_R6_89") (pintype "passive"))
    )
    (net (code "87") (name "/LCD_RESET") (class "Default")
      (node (ref "C5") (pin "2") (pintype "passive"))
      (node (ref "J1") (pin "40") (pinfunction "40_40") (pintype "passive"))
      (node (ref "LCD1") (pin "5") (pinfunction "RST_5") (pintype "passive"))
      (node (ref "R2") (pin "2") (pintype "passive"))
      (node (ref "RST") (pin "1") (pinfunction "1_1") (pintype "passive"))
      (node (ref "U1") (pin "31") (pinfunction "NRST_31") (pintype "passive"))
    )
    (net (code "88") (name "/LCD_VSYNC") (class "Default")
      (node (ref "J1") (pin "32") (pinfunction "32_32") (pintype "passive"))
      (node (ref "U1") (pin "11") (pinfunction "PI9/U4_RX/CAN1_RX/FMC_D30/LCD_VSYNC_11") (pintype "passive"))
    )
    (net (code "89") (name "/LED0") (class "Default")
      (node (ref "DS0") (pin "2") (pinfunction "K_2") (pintype "passive"))
      (node (ref "U1") (pin "107") (pinfunction "PG3/FMC_A13_107") (pintype "passive"))
    )
    (net (code "90") (name "/LED1") (class "Default")
      (node (ref "DS1") (pin "2") (pinfunction "K_2") (pintype "passive"))
      (node (ref "U1") (pin "134") (pinfunction "PI3/TIM8_ETR/SPI2_MOSI/I2S2_SD/FMC_D27/DCMI_D10_134") (pintype "passive"))
    )
    (net (code "91") (name "/OV_D0") (class "Default")
      (node (ref "M1") (pin "19") (pinfunction "Y2_19") (pintype "passive"))
      (node (ref "U1") (pin "115") (pinfunction "PC6/DFSDM_CKIN3/TIM3_CH1/TIM8_CH1/I2S2_MCK/U6_TX/FMC_NWAIT/SDMMC12_D6/DCMI_D0/LCD_HSYNC_115") (pintype "passive"))
    )
    (net (code "92") (name "/OV_D1") (class "Default")
      (node (ref "M1") (pin "21") (pinfunction "Y3_21") (pintype "passive"))
      (node (ref "U1") (pin "116") (pinfunction "PC7/DFSDM_D3/TIM3_CH2/TIM8_CH2/I2S3_MCK/U6_RX/FMC_NE1/SDMMC12_D7/DCMI_D1/LCD_G6_116") (pintype "passive"))
    )
    (net (code "93") (name "/OV_D2") (class "Default")
      (node (ref "M1") (pin "22") (pinfunction "Y4_22") (pintype "passive"))
      (node (ref "R15") (pin "1") (pintype "passive"))
      (node (ref "TF_CARD") (pin "7") (pinfunction "DAT0/DO_7") (pintype "passive"))
      (node (ref "U1") (pin "117") (pinfunction "PC8/TIM3_CH3/TIM8_CH3/U5_RTS/U6_CK/FMC_NE2/FMC_NCE/SDMMC1_D0/DCMI_D2_117") (pintype "passive"))
    )
    (net (code "94") (name "/OV_D3") (class "Default")
      (node (ref "M1") (pin "20") (pinfunction "Y5_20") (pintype "passive"))
      (node (ref "R19") (pin "1") (pintype "passive"))
      (node (ref "TF_CARD") (pin "8") (pinfunction "DAT1/IRQ_8") (pintype "passive"))
      (node (ref "U1") (pin "118") (pinfunction "PC9/MCO2/TIM3_CH4/TIM8_CH4/I2C3_SDA/I2S_CKIN/U5_CTS/QSPI_BK1_IO0/SDMMC1_D1/DCMI_D3/LCD_G3/LCD_B2_118") (pintype "passive"))
    )
    (net (code "95") (name "/OV_D4") (class "Default")
      (node (ref "M1") (pin "18") (pinfunction "Y6_18") (pintype "passive"))
      (node (ref "R17") (pin "1") (pintype "passive"))
      (node (ref "TF_CARD") (pin "2") (pinfunction "CS/DATA3_2") (pintype "passive"))
      (node (ref "U1") (pin "140") (pinfunction "PC11/DFSDM_D5/SPI3_MISO/U3_RX/U4_RX/QSPI_BK2_NCS/SDMMC1_D3/DCMI_D4_140") (pintype "passive"))
    )
    (net (code "96") (name "/OV_HREF") (class "Default")
      (node (ref "M1") (pin "9") (pinfunction "HREF_9") (pintype "passive"))
      (node (ref "U1") (pin "85") (pinfunction "PH8/I2C3_SDA/FMC_D16/DCMI_HSYNC/LCD_R2_85") (pintype "passive"))
    )
    (net (code "97") (name "/OV_PCLK") (class "Default")
      (node (ref "M1") (pin "17") (pinfunction "PCLK_17") (pintype "passive"))
      (node (ref "U1") (pin "52") (pinfunction "PA6/TIM1_BKIN/TIM3_CH1/TIM8_BKIN/SPI1_MISO/SPI6_MISO/TIM13_CH1/DCMI_PIXCLK/LCD_G2/ADC12_IN6_52") (pintype "passive"))
    )
    (net (code "98") (name "/OV_SCL") (class "Default")
      (node (ref "M1") (pin "5") (pinfunction "SIO_C_5") (pintype "passive"))
      (node (ref "U1") (pin "162") (pinfunction "PB4/NJTRST/TIM3_CH1/SPI1_MISO/SPI3_MISO/SPI2_NSS/I2S2_WS/SPI6_MISO/SDMMC2_D3/CAN3_TX/U7_TX_162") (pintype "passive"))
    )
    (net (code "99") (name "/OV_SCLK") (class "Default")
      (node (ref "M1") (pin "13") (pinfunction "XCLK_13") (pintype "passive"))
      (node (ref "Y5") (pin "3") (pinfunction "OUT_3") (pintype "passive"))
    )
    (net (code "100") (name "/OV_SDA") (class "Default")
      (node (ref "M1") (pin "3") (pinfunction "SIO_D_3") (pintype "passive"))
      (node (ref "U1") (pin "161") (pinfunction "PB3/JTDO/TIM2_CH2/SPI1_SCK/I2S1_CK/SPI3_SCK/I2S3_CK/SPI6_SCK/SDMMC2_D2/CAN3_RX/U7_RX_161") (pintype "passive"))
    )
    (net (code "101") (name "/OV_STROBE") (class "Default")
      (node (ref "M1") (pin "1") (pinfunction "STROBE_1") (pintype "passive"))
      (node (ref "MOS1") (pin "1") (pinfunction "G_1") (pintype "passive"))
      (node (ref "R41") (pin "2") (pintype "passive"))
    )
    (net (code "102") (name "/OV_VSYNC") (class "Default")
      (node (ref "M1") (pin "7") (pinfunction "VSYNC_7") (pintype "passive"))
      (node (ref "U1") (pin "165") (pinfunction "PB7/TIM4_CH2/I2C1_SDA/DFSDM_CKIN5/U1_RX/I2C4_SDA/FMC_NL/DCMI_VSYNC_165") (pintype "passive"))
    )
    (net (code "103") (name "/PA0") (class "Default")
      (node (ref "U1") (pin "40") (pinfunction "PA0/WKUP1/TIM2_CH1/TIM2_ETR/TIM5_CH1/TIM8_ETR/U2_CTS/U4_TX/SAI2_SD_B/ETH_MII_CRS/ADC123_IN0_40") (pintype "passive"))
    )
    (net (code "104") (name "/PA1") (class "Default")
      (node (ref "R40") (pin "1") (pintype "passive"))
      (node (ref "U1") (pin "41") (pinfunction "PA1/TIM2_CH2/TIM5_CH2/U2_RTS/U4_RX/QSPI_BK1_IO3/SAI2_MCK_B/ETH_MII_RX_CLK/ETH_RMII_REF_CLK/LCD_R2/ADC123_IN1_41") (pintype "passive"))
    )
    (net (code "105") (name "/PA2") (class "Default")
      (node (ref "PA2") (pin "1") (pinfunction "1_1") (pintype "passive"))
      (node (ref "U1") (pin "42") (pinfunction "PA2/TIM2_CH3/TIM5_CH3/TIM9_CH1/U2_TX/SAI2_SCK_B/ETH_MDIO/LCD_R1/ADC123_IN2/WKUP2_42") (pintype "passive"))
    )
    (net (code "106") (name "/PA3") (class "Default")
      (node (ref "PA3") (pin "1") (pinfunction "1_1") (pintype "passive"))
      (node (ref "U1") (pin "47") (pinfunction "PA3/TIM2_CH4/TIM5_CH4/TIM9_CH2/U2_RX/OTG_HS_ULPI_D0/ETH_MII_COL/LCD_B2/LCD_B5/ADC123_IN3_47") (pintype "passive"))
    )
    (net (code "107") (name "/PA4") (class "Default")
      (node (ref "J1") (pin "36") (pinfunction "36_36") (pintype "passive"))
      (node (ref "LCD1") (pin "30") (pinfunction "MOSI_30") (pintype "passive"))
      (node (ref "U1") (pin "50") (pinfunction "PA4/SPI1_NSS/I2S1_WS/SPI3_NSS/I2S3_WS/U2_CK/SPI6_NSS/OTG_HS_SOF/DCMI_HSYNC/LCD_VSYNC/ADC12_IN4/DAC_OUT1_50") (pintype "passive"))
    )
    (net (code "108") (name "/PA5") (class "Default")
      (node (ref "J1") (pin "37") (pinfunction "37_37") (pintype "passive"))
      (node (ref "LCD1") (pin "29") (pinfunction "MISO_29") (pintype "passive"))
      (node (ref "U1") (pin "51") (pinfunction "PA5/TIM2_CH1/TIM2_ETR/TIM8_CH1N/SPI1_SCK/I2S1_CK/SPI6_SCK/OTG_HS_ULPI_CK/LCD_R4/ADC12_IN5/DAC_OUT2_51") (pintype "passive"))
    )
    (net (code "109") (name "/PA7") (class "Default")
      (node (ref "J1") (pin "39") (pinfunction "39_39") (pintype "passive"))
      (node (ref "LCD1") (pin "31") (pinfunction "T_PEN_31") (pintype "passive"))
      (node (ref "U1") (pin "53") (pinfunction "PA7/TIM1_CH1N/TIM3_CH2/TIM8_CH1N/SPI1_MOSI/I2S1_SD/SPI6_MOSI/TIM14_CH1/ETH_MII_RX_DV/ETH_RMII_CRS_DV/FMC_SDNWE/ADC12_IN7_53") (pintype "passive"))
    )
    (net (code "110") (name "/PA8") (class "Default")
      (node (ref "U1") (pin "119") (pinfunction "PA8/MCO1/TIM1_CH1/TIM8_BKIN2/I2C3_SCL/U1_CK/OTG_FS_SOF/CAN3_RX/U7_RX/LCD_B3/LCD_R6_119") (pintype "passive"))
    )
    (net (code "111") (name "/PA9") (class "Default")
      (node (ref "P4") (pin "3") (pinfunction "3_3") (pintype "passive"))
      (node (ref "U1") (pin "120") (pinfunction "PA9/TIM1_CH2/I2C3_SMBA/SPI2_SCK/I2S2_CK/U1_TX/DCMI_D0/LCD_R5/OTG_FS_VBUS_120") (pintype "passive"))
    )
    (net (code "112") (name "/PA10") (class "Default")
      (node (ref "P4") (pin "1") (pinfunction "1_1") (pintype "passive"))
      (node (ref "U1") (pin "121") (pinfunction "PA10/TIM1_CH3/U1_RX/LCD_B4/LCD_B1/OTG_FS_ID/DCMI_D1_121") (pintype "passive"))
    )
    (net (code "113") (name "/PA11") (class "Default")
      (node (ref "R12") (pin "2") (pintype "passive"))
      (node (ref "U1") (pin "122") (pinfunction "PA11/TIM1_CH4/SPI2_NSS/I2S2_WS/U4_RX/U1_CTS/CAN1_RX/LCD_R4/OTG_FS_DM_122") (pintype "passive"))
    )
    (net (code "114") (name "/PA12") (class "Default")
      (node (ref "R14") (pin "2") (pintype "passive"))
      (node (ref "U1") (pin "123") (pinfunction "PA12/TIM1_ETR/SPI2_SCK/I2S2_CK/U4_TX/U1_RTS/SAI2_FS_B/CAN1_TX/LCD_R5/OTG_FS_DP_123") (pintype "passive"))
    )
    (net (code "115") (name "/PA15") (class "Default")
      (node (ref "U1") (pin "138") (pinfunction "PA15/JTDI/TIM2_CH1/TIM2_ETR/HDMI_CEC/SPI1_NSS/I2S1_WS/SPI3_NSS/I2S3_WS/SPI6_NSS/U4_RTS/CAN3_TX/U7_TX_138") (pintype "passive"))
    )
    (net (code "116") (name "/PB1") (class "Default")
      (node (ref "U1") (pin "57") (pinfunction "PB1/TIM1_CH3N/TIM3_CH4/TIM8_CH3N/DFSDM_D1/LCD_R6/OTG_HS_ULPI_D2/ETH_MII_RXD3/LCD_G0/ADC12_IN9_57") (pintype "passive"))
    )
    (net (code "117") (name "/PB2") (class "Default")
      (node (ref "U1") (pin "58") (pinfunction "PB2/SAI1_SD_A/SPI3_MOSI/I2S3_SD/QSPI_CLK/DFSDM_CKIN1_58") (pintype "passive"))
      (node (ref "U4") (pin "6") (pinfunction "CLK_6") (pintype "passive"))
    )
    (net (code "118") (name "/PB6") (class "Default")
      (node (ref "U1") (pin "164") (pinfunction "PB6/U5_TX/TIM4_CH1/HDMI_CEC/I2C1_SCL/DFSDM_D5/U1_TX/CAN2_TX/QSPI_BK1_NCS/I2C4_SCL/FMC_SDNE1/DCMI_D5_164") (pintype "passive"))
      (node (ref "U4") (pin "1") (pinfunction "~{CS}_1") (pintype "passive"))
    )
    (net (code "119") (name "/PB10") (class "Default")
      (node (ref "U1") (pin "79") (pinfunction "PB10/TIM2_CH3/I2C2_SCL/SPI2_SCK/I2S2_CK/DFSDM_D7/U3_TX/QSPI_BK1_NCS/OTG_HS_ULPI_D3/ETH_MII_RX_ER/LCD_G4_79") (pintype "passive"))
    )
    (net (code "120") (name "/PB11") (class "Default")
      (node (ref "U1") (pin "80") (pinfunction "PB11/TIM2_CH4/I2C2_SDA/DFSDM_CKIN7/U3_RX/OTG_HS_ULPI_D4/ETH_MII_TX_EN/ETH_RMII_TX_EN/LCD_G5_80") (pintype "passive"))
    )
    (net (code "121") (name "/PB12") (class "Default")
      (node (ref "U1") (pin "92") (pinfunction "PB12/TIM1_BKIN/I2C2_SMBA/SPI2_NSS/I2S2_WS/DFSDM_D1/U3_CK/U5_RX/CAN2_RX/OTG_HS_ULPI_D5/ETH_MII_TXD0/ETH_RMII_TXD0/OTG_HS_ID_92") (pintype "passive"))
    )
    (net (code "122") (name "/PB13") (class "Default")
      (node (ref "U1") (pin "93") (pinfunction "PB13/TIM1_CH1N/SPI2_SCK/I2S2_CK/DFSDM_CKIN1/U3_CTS/U5_TX/CAN2_TX/OTG_HS_ULPI_D6/ETH_MII_TXD1/ETH_RMII_TXD1/OTG_HS_VBUS_93") (pintype "passive"))
    )
    (net (code "123") (name "/PB14") (class "Default")
      (node (ref "U1") (pin "94") (pinfunction "PB14/TIM1_CH2N/TIM8_CH2N/U1_TX/SPI2_MISO/DFSDM_D2/U3_RTS/U4_RTS/SDMMC2_D0/TIM12_CH1/OTG_HS_DM_94") (pintype "passive"))
    )
    (net (code "124") (name "/PB15") (class "Default")
      (node (ref "U1") (pin "95") (pinfunction "PB15/RTC_REFIN/TIM1_CH3N/TIM8_CH3N/U1_RX/SPI2_MOSI/I2S2_SD/DFSDM_CKIN2/U4_CTS/SDMMC2_D1/TIM12_CH2/OTG_HS_DP_95") (pintype "passive"))
    )
    (net (code "125") (name "/PC1") (class "Default")
      (node (ref "U1") (pin "33") (pinfunction "PC1/DFSDM_CKIN4/DFSDM_D0/SPI2_MOSI/I2S2_SD/SAI1_SD_A/ETH_MDC/ADC123_IN11/RTC_TAMP3/WKUP3_33") (pintype "passive"))
    )
    (net (code "126") (name "/PC4") (class "Default")
      (node (ref "J1") (pin "38") (pinfunction "38_38") (pintype "passive"))
      (node (ref "LCD1") (pin "34") (pinfunction "CLK_34") (pintype "passive"))
      (node (ref "U1") (pin "54") (pinfunction "PC4/DFSDM_CKIN2/I2S1_MCK/SPDIFRX_IN2/ETH_MII_RXD0/ETH_RMII_RXD0/FMC_SDNE0/ADC12_IN14_54") (pintype "passive"))
    )
    (net (code "127") (name "/PC5") (class "Default")
      (node (ref "J1") (pin "35") (pinfunction "35_35") (pintype "passive"))
      (node (ref "LCD1") (pin "33") (pinfunction "T_CS_33") (pintype "passive"))
      (node (ref "U1") (pin "55") (pinfunction "PC5/DFSDM_D2/SPDIFRX_IN3/ETH_MII_RXD1/ETH_RMII_RXD1/FMC_SDCKE0/ADC12_IN15_55") (pintype "passive"))
    )
    (net (code "128") (name "/PC10") (class "Default")
      (node (ref "R18") (pin "1") (pintype "passive"))
      (node (ref "TF_CARD") (pin "1") (pinfunction "DAT2/NC_1") (pintype "passive"))
      (node (ref "U1") (pin "139") (pinfunction "PC10/DFSDM_CKIN5/SPI3_SCK/I2S3_CK/U3_TX/U4_TX/QSPI_BK1_IO1/SDMMC1_D2/DCMI_D8/LCD_R2_139") (pintype "passive"))
    )
    (net (code "129") (name "/PC12") (class "Default")
      (node (ref "TF_CARD") (pin "5") (pinfunction "CLK_5") (pintype "passive"))
      (node (ref "U1") (pin "141") (pinfunction "PC12/SPI3_MOSI/I2S3_SD/U3_CK/U5_TX/SDMMC1_CK/DCMI_D9_141") (pintype "passive"))
    )
    (net (code "130") (name "/PC13") (class "Default")
      (node (ref "U1") (pin "8") (pinfunction "PC13/RTC_TAMP1/RTC_TS/RTC_OUT/WKUP4_8") (pintype "passive"))
    )
    (net (code "131") (name "/PC14") (class "Default")
      (node (ref "C3") (pin "2") (pintype "passive"))
      (node (ref "U1") (pin "9") (pinfunction "PC14/OSC32_IN_9") (pintype "passive"))
      (node (ref "Y2") (pin "2") (pinfunction "OSC2_2") (pintype "passive"))
    )
    (net (code "132") (name "/PC15") (class "Default")
      (node (ref "C4") (pin "2") (pintype "passive"))
      (node (ref "U1") (pin "10") (pinfunction "PC15/OSC32_OUT_10") (pintype "passive"))
      (node (ref "Y2") (pin "1") (pinfunction "OSC1_1") (pintype "passive"))
    )
    (net (code "133") (name "/PD2") (class "Default")
      (node (ref "R16") (pin "1") (pintype "passive"))
      (node (ref "TF_CARD") (pin "3") (pinfunction "CMD_3") (pintype "passive"))
      (node (ref "U1") (pin "144") (pinfunction "PD2/TIM3_ETR/U5_RX/SDMMC1_CMD/DCMI_D11_144") (pintype "passive"))
    )
    (net (code "134") (name "/PE2") (class "Default")
      (node (ref "U1") (pin "1") (pinfunction "PE2/SPI4_SCK/SAI1_MCLK_A/QSPI_BK1_IO2/ETH_MII_TXD3/FMC_A23_1") (pintype "passive"))
      (node (ref "U2") (pin "11") (pinfunction "MCLK_11") (pintype "passive"))
    )
    (net (code "135") (name "/PE3") (class "Default")
      (node (ref "U1") (pin "2") (pinfunction "PE3/SAI1_SD_B/FMC_A19_2") (pintype "passive"))
      (node (ref "U2") (pin "9") (pinfunction "ADCDAT_9") (pintype "passive"))
    )
    (net (code "136") (name "/PE4") (class "Default")
      (node (ref "U1") (pin "3") (pinfunction "PE4/DFSDM_D3/SPI4_NSS/SAI1_FS_A/FMC_A20/DCMI_D4/LCD_B0_3") (pintype "passive"))
      (node (ref "U2") (pin "7") (pinfunction "LRC_7") (pintype "passive"))
    )
    (net (code "137") (name "/PE5") (class "Default")
      (node (ref "U1") (pin "4") (pinfunction "PE5/DFSDM_CKIN3/TIM9_CH1/SPI4_MISO/SAI1_SCK_A/FMC_A21/DCMI_D6/LCD_G0_4") (pintype "passive"))
      (node (ref "U2") (pin "8") (pinfunction "BCLK_8") (pintype "passive"))
    )
    (net (code "138") (name "/PE6") (class "Default")
      (node (ref "U1") (pin "5") (pinfunction "PE6/TIM1_BKIN2/TIM9_CH2/SPI4_MOSI/SAI1_SD_A/SAI2_MCK_B/FMC_A22/DCMI_D7/LCD_G1_5") (pintype "passive"))
      (node (ref "U2") (pin "10") (pinfunction "DACDAT_10") (pintype "passive"))
    )
    (net (code "139") (name "/PG13") (class "Default")
      (node (ref "U1") (pin "156") (pinfunction "PG13/LPTIM1_OUT/SPI6_SCK/U6_CTS/ETH_MII_TXD0/ETH_RMII_TXD0/FMC_A24/LCD_R0_156") (pintype "passive"))
    )
    (net (code "140") (name "/PG14") (class "Default")
      (node (ref "U1") (pin "157") (pinfunction "PG14/LPTIM1_ETR/SPI6_MOSI/U6_TX/QSPI_BK2_IO3/ETH_MII_TXD1/ETH_RMII_TXD1/FMC_A25/LCD_B0_157") (pintype "passive"))
    )
    (net (code "141") (name "/PH0") (class "Default")
      (node (ref "C1") (pin "1") (pintype "passive"))
      (node (ref "U1") (pin "29") (pinfunction "PH0/OSC_IN_29") (pintype "passive"))
      (node (ref "Y1") (pin "2") (pinfunction "OSC2_2") (pintype "passive"))
    )
    (net (code "142") (name "/PH1") (class "Default")
      (node (ref "C2") (pin "1") (pintype "passive"))
      (node (ref "U1") (pin "30") (pinfunction "PH1/OSC_OUT_30") (pintype "passive"))
      (node (ref "Y1") (pin "1") (pinfunction "OSC1_1") (pintype "passive"))
    )
    (net (code "143") (name "/PH2") (class "Default")
      (node (ref "U1") (pin "43") (pinfunction "PH2/LPTIM1_IN2/QSPI_BK2_IO0/SAI2_SCK_B/ETH_MII_CRS/FMC_SDCKE0/LCD_R0_43") (pintype "passive"))
    )
    (net (code "144") (name "/PH3") (class "Default")
      (node (ref "U1") (pin "44") (pinfunction "PH3/QSPI_BK2_IO1/SAI2_MCK_B/ETH_MII_COL/FMC_SDNE0/LCD_R1_44") (pintype "passive"))
    )
    (net (code "145") (name "/PH6") (class "Default")
      (node (ref "U1") (pin "83") (pinfunction "PH6/I2C2_SMBA/SPI5_SCK/TIM12_CH1/ETH_MII_RXD2/FMC_SDNE1/DCMI_D8_83") (pintype "passive"))
    )
    (net (code "146") (name "/PH7") (class "Default")
      (node (ref "U1") (pin "84") (pinfunction "PH7/I2C3_SCL/SPI5_MISO/ETH_MII_RXD3/FMC_SDCKE1/DCMI_D9_84") (pintype "passive"))
    )
    (net (code "147") (name "/PI11") (class "Default")
      (node (ref "U1") (pin "13") (pinfunction "PI11/LCD_G6/OTG_HS_ULPI_DIR/WKUP6_13") (pintype "passive"))
    )
    (net (code "148") (name "/VUSB") (class "Default")
      (node (ref "POWER") (pin "2") (pinfunction "TAP_2") (pintype "passive"))
      (node (ref "USB_232") (pin "1") (pinfunction "VCC_1") (pintype "passive"))
      (node (ref "USB_SLAVE") (pin "1") (pinfunction "VCC_1") (pintype "passive"))
    )
    (net (code "149") (name "AF_AVDD") (class "Default")
      (node (ref "C74") (pin "2") (pintype "passive"))
      (node (ref "C75") (pin "2") (pintype "passive"))
      (node (ref "L3") (pin "1") (pintype "passive"))
      (node (ref "M1") (pin "4") (pinfunction "AVDD_4") (pintype "passive"))
    )
    (net (code "150") (name "AF_DO_VDD") (class "Default")
      (node (ref "C76") (pin "2") (pintype "passive"))
      (node (ref "C77") (pin "2") (pintype "passive"))
      (node (ref "L4") (pin "1") (pintype "passive"))
      (node (ref "M1") (pin "11") (pinfunction "DOVDD_11") (pintype "passive"))
    )
    (net (code "151") (name "AF_VCC") (class "Default")
      (node (ref "C82") (pin "2") (pintype "passive"))
      (node (ref "C83") (pin "2") (pintype "passive"))
      (node (ref "M1") (pin "24") (pinfunction "AF-VCC_24") (pintype "passive"))
      (node (ref "U8") (pin "2") (pinfunction "VOUT_2") (pintype "passive"))
    )
    (net (code "152") (name "AGND") (class "Default")
      (node (ref "AUX") (pin "3") (pinfunction "COM_3") (pintype "passive"))
      (node (ref "C51") (pin "2") (pintype "passive"))
      (node (ref "C52") (pin "2") (pintype "passive"))
      (node (ref "C67") (pin "1") (pintype "passive"))
      (node (ref "C68") (pin "1") (pintype "passive"))
      (node (ref "MIC1") (pin "3") (pinfunction "COM_3") (pintype "passive"))
      (node (ref "PHONE") (pin "3") (pinfunction "COM_3") (pintype "passive"))
      (node (ref "R31") (pin "2") (pintype "passive"))
      (node (ref "R34") (pin "1") (pintype "passive"))
      (node (ref "R35") (pin "1") (pintype "passive"))
      (node (ref "R66") (pin "1") (pintype "passive"))
      (node (ref "U2") (pin "28") (pinfunction "AGND_28") (pintype "passive"))
    )
    (net (code "153") (name "GND") (class "Default")
      (node (ref "C1") (pin "2") (pintype "passive"))
      (node (ref "C10") (pin "1") (pintype "passive"))
      (node (ref "C11") (pin "1") (pintype "passive"))
      (node (ref "C12") (pin "1") (pintype "passive"))
      (node (ref "C13") (pin "1") (pintype "passive"))
      (node (ref "C14") (pin "1") (pintype "passive"))
      (node (ref "C15") (pin "1") (pintype "passive"))
      (node (ref "C16") (pin "1") (pintype "passive"))
      (node (ref "C17") (pin "1") (pintype "passive"))
      (node (ref "C18") (pin "1") (pintype "passive"))
      (node (ref "C19") (pin "1") (pintype "passive"))
      (node (ref "C2") (pin "2") (pintype "passive"))
      (node (ref "C20") (pin "1") (pintype "passive"))
      (node (ref "C21") (pin "1") (pintype "passive"))
      (node (ref "C22") (pin "1") (pintype "passive"))
      (node (ref "C23") (pin "1") (pintype "passive"))
      (node (ref "C24") (pin "1") (pintype "passive"))
      (node (ref "C25") (pin "1") (pintype "passive"))
      (node (ref "C26") (pin "1") (pintype "passive"))
      (node (ref "C27") (pin "1") (pintype "passive"))
      (node (ref "C28") (pin "1") (pintype "passive"))
      (node (ref "C29") (pin "1") (pintype "passive"))
      (node (ref "C3") (pin "1") (pintype "passive"))
      (node (ref "C30") (pin "2") (pintype "passive"))
      (node (ref "C31") (pin "2") (pintype "passive"))
      (node (ref "C32") (pin "2") (pintype "passive"))
      (node (ref "C33") (pin "1") (pintype "passive"))
      (node (ref "C34") (pin "1") (pintype "passive"))
      (node (ref "C35") (pin "2") (pinfunction "GND_2") (pintype "passive"))
      (node (ref "C36") (pin "2") (pintype "passive"))
      (node (ref "C38") (pin "2") (pintype "passive"))
      (node (ref "C39") (pin "2") (pintype "passive"))
      (node (ref "C4") (pin "1") (pintype "passive"))
      (node (ref "C40") (pin "1") (pintype "passive"))
      (node (ref "C41") (pin "1") (pintype "passive"))
      (node (ref "C42") (pin "1") (pintype "passive"))
      (node (ref "C43") (pin "1") (pintype "passive"))
      (node (ref "C44") (pin "1") (pintype "passive"))
      (node (ref "C45") (pin "1") (pintype "passive"))
      (node (ref "C46") (pin "1") (pintype "passive"))
      (node (ref "C47") (pin "1") (pintype "passive"))
      (node (ref "C48") (pin "1") (pintype "passive"))
      (node (ref "C49") (pin "2") (pintype "passive"))
      (node (ref "C5") (pin "1") (pintype "passive"))
      (node (ref "C50") (pin "1") (pintype "passive"))
      (node (ref "C55") (pin "1") (pintype "passive"))
      (node (ref "C56") (pin "1") (pintype "passive"))
      (node (ref "C57") (pin "1") (pintype "passive"))
      (node (ref "C58") (pin "1") (pintype "passive"))
      (node (ref "C6") (pin "1") (pintype "passive"))
      (node (ref "C69") (pin "1") (pintype "passive"))
      (node (ref "C7") (pin "1") (pintype "passive"))
      (node (ref "C70") (pin "1") (pintype "passive"))
      (node (ref "C71") (pin "1") (pintype "passive"))
      (node (ref "C72") (pin "1") (pintype "passive"))
      (node (ref "C73") (pin "1") (pintype "passive"))
      (node (ref "C74") (pin "1") (pintype "passive"))
      (node (ref "C75") (pin "1") (pintype "passive"))
      (node (ref "C76") (pin "1") (pintype "passive"))
      (node (ref "C77") (pin "1") (pintype "passive"))
      (node (ref "C78") (pin "1") (pintype "passive"))
      (node (ref "C79") (pin "1") (pintype "passive"))
      (node (ref "C8") (pin "1") (pintype "passive"))
      (node (ref "C80") (pin "1") (pintype "passive"))
      (node (ref "C81") (pin "1") (pintype "passive"))
      (node (ref "C82") (pin "1") (pintype "passive"))
      (node (ref "C83") (pin "1") (pintype "passive"))
      (node (ref "C84") (pin "2") (pintype "passive"))
      (node (ref "C9") (pin "1") (pintype "passive"))
      (node (ref "J1") (pin "11") (pinfunction "11_11") (pintype "passive"))
      (node (ref "J1") (pin "12") (pinfunction "12_12") (pintype "passive"))
      (node (ref "J1") (pin "13") (pinfunction "13_13") (pintype "passive"))
      (node (ref "J1") (pin "20") (pinfunction "20_20") (pintype "passive"))
      (node (ref "J1") (pin "21") (pinfunction "21_21") (pintype "passive"))
      (node (ref "J1") (pin "22") (pinfunction "22_22") (pintype "passive"))
      (node (ref "J1") (pin "23") (pinfunction "23_23") (pintype "passive"))
      (node (ref "J1") (pin "29") (pinfunction "29_29") (pintype "passive"))
      (node (ref "J1") (pin "3") (pinfunction "3_3") (pintype "passive"))
      (node (ref "J1") (pin "4") (pinfunction "4_4") (pintype "passive"))
      (node (ref "J1") (pin "5") (pinfunction "5_5") (pintype "passive"))
      (node (ref "LCD1") (pin "22") (pinfunction "GND_22") (pintype "passive"))
      (node (ref "LCD1") (pin "26") (pinfunction "GND_26") (pintype "passive"))
      (node (ref "LCD1") (pin "27") (pinfunction "GND_27") (pintype "passive"))
      (node (ref "M1") (pin "15") (pinfunction "DGND_15") (pintype "passive"))
      (node (ref "M1") (pin "2") (pinfunction "AGND_2") (pintype "passive"))
      (node (ref "M1") (pin "23") (pinfunction "AF-GND_23") (pintype "passive"))
      (node (ref "M1") (pin "25") (pinfunction "DGND_25") (pintype "passive"))
      (node (ref "M1") (pin "26") (pinfunction "DGND_26") (pintype "passive"))
      (node (ref "MOS1") (pin "2") (pinfunction "S_2") (pintype "passive"))
      (node (ref "P10") (pin "1") (pinfunction "1_1") (pintype "passive"))
      (node (ref "PWR") (pin "2") (pinfunction "K_2") (pintype "passive"))
      (node (ref "R1") (pin "2") (pintype "passive"))
      (node (ref "R28") (pin "1") (pintype "passive"))
      (node (ref "R31") (pin "1") (pintype "passive"))
      (node (ref "R32") (pin "1") (pintype "passive"))
      (node (ref "R41") (pin "1") (pintype "passive"))
      (node (ref "R8") (pin "2") (pintype "passive"))
      (node (ref "R9") (pin "2") (pintype "passive"))
      (node (ref "RST") (pin "2") (pinfunction "2_2") (pintype "passive"))
      (node (ref "TF_CARD") (pin "6") (pinfunction "VSS_6") (pintype "passive"))
      (node (ref "U1") (pin "102") (pinfunction "VSS_102") (pintype "passive"))
      (node (ref "U1") (pin "113") (pinfunction "VSS_113") (pintype "passive"))
      (node (ref "U1") (pin "126") (pinfunction "VSS_126") (pintype "passive"))
      (node (ref "U1") (pin "135") (pinfunction "VSS_135") (pintype "passive"))
      (node (ref "U1") (pin "14") (pinfunction "VSS_14") (pintype "passive"))
      (node (ref "U1") (pin "148") (pinfunction "VSS_148") (pintype "passive"))
      (node (ref "U1") (pin "158") (pinfunction "VSS_158") (pintype "passive"))
      (node (ref "U1") (pin "22") (pinfunction "VSS_22") (pintype "passive"))
      (node (ref "U1") (pin "37") (pinfunction "VSSA_37") (pintype "passive"))
      (node (ref "U1") (pin "61") (pinfunction "VSS_61") (pintype "passive"))
      (node (ref "U1") (pin "71") (pinfunction "VSS_71") (pintype "passive"))
      (node (ref "U1") (pin "90") (pinfunction "VSS_90") (pintype "passive"))
      (node (ref "U10") (pin "13") (pinfunction "VSS_13") (pintype "passive"))
      (node (ref "U10") (pin "36") (pinfunction "VSS_36") (pintype "passive"))
      (node (ref "U11") (pin "12") (pinfunction "VSSQ1_12") (pintype "power_in"))
      (node (ref "U11") (pin "28") (pinfunction "VSS2_28") (pintype "power_in"))
      (node (ref "U11") (pin "41") (pinfunction "VSS0_41") (pintype "power_in"))
      (node (ref "U11") (pin "46") (pinfunction "VSSQ2_46") (pintype "power_in"))
      (node (ref "U11") (pin "52") (pinfunction "VSSQ3_52") (pintype "power_in"))
      (node (ref "U11") (pin "54") (pinfunction "VSS1_54") (pintype "power_in"))
      (node (ref "U11") (pin "6") (pinfunction "VSSQ0_6") (pintype "power_in"))
      (node (ref "U12") (pin "1") (pinfunction "GND_1") (pintype "passive"))
      (node (ref "U14") (pin "1") (pinfunction "GND_1") (pintype "passive"))
      (node (ref "U2") (pin "12") (pinfunction "DGND_12") (pintype "passive"))
      (node (ref "U2") (pin "24") (pinfunction "SPKGND_24") (pintype "passive"))
      (node (ref "U2") (pin "33") (pinfunction "GNDPAD_33") (pintype "passive"))
      (node (ref "U3") (pin "1") (pinfunction "A0_1") (pintype "passive"))
      (node (ref "U3") (pin "2") (pinfunction "A1_2") (pintype "passive"))
      (node (ref "U3") (pin "3") (pinfunction "A2_3") (pintype "passive"))
      (node (ref "U3") (pin "4") (pinfunction "GND_4") (pintype "passive"))
      (node (ref "U3") (pin "7") (pinfunction "WP_7") (pintype "passive"))
      (node (ref "U4") (pin "4") (pinfunction "GND_4") (pintype "passive"))
      (node (ref "U5") (pin "1") (pinfunction "GND_1") (pintype "passive"))
      (node (ref "U6") (pin "3") (pinfunction "NC_3") (pintype "passive"))
      (node (ref "U6") (pin "4") (pinfunction "GND_4") (pintype "passive"))
      (node (ref "U8") (pin "1") (pinfunction "GND_1") (pintype "passive"))
      (node (ref "U9") (pin "1") (pinfunction "GND_1") (pintype "passive"))
      (node (ref "USB_232") (pin "5") (pinfunction "GND_5") (pintype "passive"))
      (node (ref "USB_SLAVE") (pin "5") (pinfunction "GND_5") (pintype "passive"))
      (node (ref "Y5") (pin "2") (pinfunction "GND_2") (pintype "passive"))
    )
    (net (code "154") (name "Net-(AUX-CHL)") (class "Default")
      (node (ref "AUX") (pin "1") (pinfunction "CHL_1") (pintype "passive"))
      (node (ref "C66") (pin "2") (pintype "passive"))
    )
    (net (code "155") (name "Net-(AUX-CHR)") (class "Default")
      (node (ref "AUX") (pin "2") (pinfunction "CHR_2") (pintype "passive"))
      (node (ref "C65") (pin "2") (pintype "passive"))
    )
    (net (code "156") (name "Net-(C40-Pad2)") (class "Default")
      (node (ref "C40") (pin "2") (pintype "passive"))
      (node (ref "C41") (pin "2") (pintype "passive"))
      (node (ref "R20") (pin "1") (pintype "passive"))
      (node (ref "U10") (pin "12") (pinfunction "VCC_12") (pintype "passive"))
      (node (ref "U10") (pin "37") (pinfunction "VCC_37") (pintype "passive"))
    )
    (net (code "157") (name "Net-(C53-GND)") (class "Default")
      (node (ref "C53") (pin "2") (pinfunction "GND_2") (pintype "passive"))
      (node (ref "PHONE") (pin "2") (pinfunction "CHR_2") (pintype "passive"))
    )
    (net (code "158") (name "Net-(C53-VCC)") (class "Default")
      (node (ref "C53") (pin "1") (pinfunction "VCC_1") (pintype "passive"))
      (node (ref "U2") (pin "29") (pinfunction "ROUT1_29") (pintype "passive"))
    )
    (net (code "159") (name "Net-(C54-GND)") (class "Default")
      (node (ref "C54") (pin "2") (pinfunction "GND_2") (pintype "passive"))
      (node (ref "PHONE") (pin "1") (pinfunction "CHL_1") (pintype "passive"))
    )
    (net (code "160") (name "Net-(C54-VCC)") (class "Default")
      (node (ref "C54") (pin "1") (pinfunction "VCC_1") (pintype "passive"))
      (node (ref "U2") (pin "30") (pinfunction "LOUT1_30") (pintype "passive"))
    )
    (net (code "161") (name "Net-(DS0-A)") (class "Default")
      (node (ref "DS0") (pin "1") (pinfunction "A_1") (pintype "passive"))
      (node (ref "R37") (pin "1") (pintype "passive"))
    )
    (net (code "162") (name "Net-(DS1-A)") (class "Default")
      (node (ref "DS1") (pin "1") (pinfunction "A_1") (pintype "passive"))
      (node (ref "R38") (pin "1") (pintype "passive"))
    )
    (net (code "163") (name "Net-(MIC-GND)") (class "Default")
      (node (ref "C61") (pin "2") (pintype "passive"))
      (node (ref "C63") (pin "2") (pintype "passive"))
      (node (ref "MIC") (pin "2") (pinfunction "GND_2") (pintype "passive"))
      (node (ref "R33") (pin "2") (pintype "passive"))
      (node (ref "R34") (pin "2") (pintype "passive"))
      (node (ref "R66") (pin "2") (pintype "passive"))
    )
    (net (code "164") (name "Net-(MIC-VCC)") (class "Default")
      (node (ref "C62") (pin "2") (pintype "passive"))
      (node (ref "C64") (pin "2") (pintype "passive"))
      (node (ref "MIC") (pin "1") (pinfunction "VCC_1") (pintype "passive"))
      (node (ref "R35") (pin "2") (pintype "passive"))
    )
    (net (code "165") (name "Net-(MIC1-CHL)") (class "Default")
      (node (ref "C60") (pin "2") (pintype "passive"))
      (node (ref "MIC1") (pin "1") (pinfunction "CHL_1") (pintype "passive"))
    )
    (net (code "166") (name "Net-(MIC1-CHR)") (class "Default")
      (node (ref "C59") (pin "2") (pintype "passive"))
      (node (ref "MIC1") (pin "2") (pinfunction "CHR_2") (pintype "passive"))
    )
    (net (code "167") (name "Net-(MOS1-D)") (class "Default")
      (node (ref "LED5") (pin "2") (pinfunction "2_2") (pintype "passive"))
      (node (ref "MOS1") (pin "3") (pinfunction "D_3") (pintype "passive"))
    )
    (net (code "168") (name "Net-(PWR-A)") (class "Default")
      (node (ref "PWR") (pin "1") (pinfunction "A_1") (pintype "passive"))
      (node (ref "R39") (pin "1") (pintype "passive"))
    )
    (net (code "169") (name "Net-(U1-BYPASS_REG)") (class "Default")
      (node (ref "R1") (pin "1") (pintype "passive"))
      (node (ref "U1") (pin "48") (pinfunction "BYPASS_REG_48") (pintype "passive"))
    )
    (net (code "170") (name "Net-(U1-PDR_ON)") (class "Default")
      (node (ref "R5") (pin "1") (pintype "passive"))
      (node (ref "U1") (pin "171") (pinfunction "PDR_ON_171") (pintype "passive"))
    )
    (net (code "171") (name "Net-(U1-VBAT)") (class "Default")
      (node (ref "C8") (pin "2") (pintype "passive"))
      (node (ref "D1") (pin "2") (pintype "passive"))
      (node (ref "U1") (pin "6") (pinfunction "VBAT_6") (pintype "passive"))
    )
    (net (code "172") (name "Net-(U1-VCAP_1)") (class "Default")
      (node (ref "C6") (pin "2") (pintype "passive"))
      (node (ref "U1") (pin "81") (pinfunction "VCAP_1_81") (pintype "passive"))
    )
    (net (code "173") (name "Net-(U1-VCAP_2)") (class "Default")
      (node (ref "C7") (pin "2") (pintype "passive"))
      (node (ref "U1") (pin "125") (pinfunction "VCAP_2_125") (pintype "passive"))
    )
    (net (code "174") (name "Net-(U1-VDDA)") (class "Default")
      (node (ref "C11") (pin "2") (pintype "passive"))
      (node (ref "C12") (pin "2") (pintype "passive"))
      (node (ref "R3") (pin "1") (pintype "passive"))
      (node (ref "R4") (pin "1") (pintype "passive"))
      (node (ref "U1") (pin "39") (pinfunction "VDDA_39") (pintype "passive"))
    )
    (net (code "175") (name "Net-(U1-VREF+)") (class "Default")
      (node (ref "C10") (pin "2") (pintype "passive"))
      (node (ref "C9") (pin "2") (pintype "passive"))
      (node (ref "R3") (pin "2") (pintype "passive"))
      (node (ref "U1") (pin "38") (pinfunction "VREF+_38") (pintype "passive"))
    )
    (net (code "176") (name "Net-(U2-AUXL)") (class "Default")
      (node (ref "C65") (pin "1") (pintype "passive"))
      (node (ref "U2") (pin "19") (pinfunction "AUXL_19") (pintype "passive"))
    )
    (net (code "177") (name "Net-(U2-AUXR)") (class "Default")
      (node (ref "C66") (pin "1") (pintype "passive"))
      (node (ref "U2") (pin "20") (pinfunction "AUXR_20") (pintype "passive"))
    )
    (net (code "178") (name "Net-(U2-DBVDD)") (class "Default")
      (node (ref "C57") (pin "2") (pintype "passive"))
      (node (ref "C58") (pin "2") (pintype "passive"))
      (node (ref "R30") (pin "2") (pintype "passive"))
      (node (ref "U2") (pin "13") (pinfunction "DCVDD_13") (pintype "passive"))
      (node (ref "U2") (pin "14") (pinfunction "DBVDD_14") (pintype "passive"))
    )
    (net (code "179") (name "Net-(U2-L2{slash}GPIO2)") (class "Default")
      (node (ref "C59") (pin "1") (pintype "passive"))
      (node (ref "U2") (pin "3") (pinfunction "L2/GPIO2_3") (pintype "passive"))
    )
    (net (code "180") (name "Net-(U2-LIN)") (class "Default")
      (node (ref "C62") (pin "1") (pintype "passive"))
      (node (ref "U2") (pin "2") (pinfunction "LIN_2") (pintype "passive"))
    )
    (net (code "181") (name "Net-(U2-LIP)") (class "Default")
      (node (ref "C61") (pin "1") (pintype "passive"))
      (node (ref "U2") (pin "1") (pinfunction "LIP_1") (pintype "passive"))
    )
    (net (code "182") (name "Net-(U2-LOUT2)") (class "Default")
      (node (ref "SPK+") (pin "1") (pinfunction "1_1") (pintype "passive"))
      (node (ref "U2") (pin "25") (pinfunction "LOUT2_25") (pintype "passive"))
    )
    (net (code "183") (name "Net-(U2-MICBIAS)") (class "Default")
      (node (ref "C68") (pin "2") (pintype "passive"))
      (node (ref "R33") (pin "1") (pintype "passive"))
      (node (ref "U2") (pin "32") (pinfunction "MICBIAS_32") (pintype "passive"))
    )
    (net (code "184") (name "Net-(U2-MODE)") (class "Default")
      (node (ref "R32") (pin "2") (pintype "passive"))
      (node (ref "U2") (pin "18") (pinfunction "MODE_18") (pintype "passive"))
    )
    (net (code "185") (name "Net-(U2-R2{slash}GPIO3)") (class "Default")
      (node (ref "C60") (pin "1") (pintype "passive"))
      (node (ref "U2") (pin "6") (pinfunction "R2/GPIO3_6") (pintype "passive"))
    )
    (net (code "186") (name "Net-(U2-RIN)") (class "Default")
      (node (ref "C64") (pin "1") (pintype "passive"))
      (node (ref "U2") (pin "5") (pinfunction "RIN_5") (pintype "passive"))
    )
    (net (code "187") (name "Net-(U2-RIP)") (class "Default")
      (node (ref "C63") (pin "1") (pintype "passive"))
      (node (ref "U2") (pin "4") (pinfunction "RIP_4") (pintype "passive"))
    )
    (net (code "188") (name "Net-(U2-ROUT2)") (class "Default")
      (node (ref "SPK-") (pin "1") (pinfunction "1_1") (pintype "passive"))
      (node (ref "U2") (pin "23") (pinfunction "ROUT2_23") (pintype "passive"))
    )
    (net (code "189") (name "Net-(U2-SPKVDD)") (class "Default")
      (node (ref "C55") (pin "2") (pintype "passive"))
      (node (ref "C56") (pin "2") (pintype "passive"))
      (node (ref "R29") (pin "1") (pintype "passive"))
      (node (ref "U2") (pin "26") (pinfunction "SPKVDD_26") (pintype "passive"))
    )
    (net (code "190") (name "Net-(U2-VMID)") (class "Default")
      (node (ref "C67") (pin "2") (pintype "passive"))
      (node (ref "U2") (pin "27") (pinfunction "VMID_27") (pintype "passive"))
    )
    (net (code "191") (name "Net-(U5-VIN)") (class "Default")
      (node (ref "C78") (pin "2") (pintype "passive"))
      (node (ref "L5") (pin "2") (pintype "passive"))
      (node (ref "U5") (pin "3") (pinfunction "VIN_3") (pintype "passive"))
    )
    (net (code "192") (name "Net-(U5-VOUT)") (class "Default")
      (node (ref "L6") (pin "1") (pintype "passive"))
      (node (ref "U5") (pin "2") (pinfunction "VOUT_2") (pintype "passive"))
    )
    (net (code "193") (name "Net-(U10-~{WP})") (class "Default")
      (node (ref "R21") (pin "1") (pintype "passive"))
      (node (ref "U10") (pin "19") (pinfunction "~{WP}_19") (pintype "passive"))
    )
    (net (code "194") (name "Net-(U14-D+)") (class "Default")
      (node (ref "U14") (pin "5") (pinfunction "D+_5") (pintype "passive"))
      (node (ref "USB_232") (pin "3") (pinfunction "D+_3") (pintype "passive"))
    )
    (net (code "195") (name "Net-(U14-D-)") (class "Default")
      (node (ref "U14") (pin "6") (pinfunction "D-_6") (pintype "passive"))
      (node (ref "USB_232") (pin "2") (pinfunction "D-_2") (pintype "passive"))
    )
    (net (code "196") (name "Net-(U14-V3)") (class "Default")
      (node (ref "C28") (pin "2") (pintype "passive"))
      (node (ref "U14") (pin "4") (pinfunction "V3_4") (pintype "passive"))
    )
    (net (code "197") (name "Net-(U14-XI)") (class "Default")
      (node (ref "C29") (pin "2") (pintype "passive"))
      (node (ref "U14") (pin "7") (pinfunction "XI_7") (pintype "passive"))
      (node (ref "Y3") (pin "1") (pinfunction "OSC1_1") (pintype "passive"))
    )
    (net (code "198") (name "Net-(U14-XO)") (class "Default")
      (node (ref "C30") (pin "1") (pintype "passive"))
      (node (ref "U14") (pin "8") (pinfunction "XO_8") (pintype "passive"))
      (node (ref "Y3") (pin "2") (pinfunction "OSC2_2") (pintype "passive"))
    )
    (net (code "199") (name "Net-(USB_SLAVE-D+)") (class "Default")
      (node (ref "R13") (pin "1") (pintype "passive"))
      (node (ref "R14") (pin "1") (pintype "passive"))
      (node (ref "USB_SLAVE") (pin "3") (pinfunction "D+_3") (pintype "passive"))
    )
    (net (code "200") (name "Net-(USB_SLAVE-D-)") (class "Default")
      (node (ref "R12") (pin "1") (pintype "passive"))
      (node (ref "USB_SLAVE") (pin "2") (pinfunction "D-_2") (pintype "passive"))
    )
    (net (code "201") (name "Net-(Y5-VCC)") (class "Default")
      (node (ref "C70") (pin "2") (pintype "passive"))
      (node (ref "L2") (pin "1") (pintype "passive"))
      (node (ref "Y5") (pin "4") (pinfunction "VCC_4") (pintype "passive"))
    )
    (net (code "202") (name "VCC1.5") (class "Default")
      (node (ref "C79") (pin "2") (pintype "passive"))
      (node (ref "C80") (pin "2") (pintype "passive"))
      (node (ref "C84") (pin "1") (pintype "passive"))
      (node (ref "L6") (pin "2") (pintype "passive"))
      (node (ref "M1") (pin "10") (pinfunction "DVDD_10") (pintype "passive"))
    )
    (net (code "203") (name "VCC2.8") (class "Default")
      (node (ref "C72") (pin "2") (pintype "passive"))
      (node (ref "C73") (pin "2") (pintype "passive"))
      (node (ref "L3") (pin "2") (pintype "passive"))
      (node (ref "L4") (pin "2") (pintype "passive"))
      (node (ref "L5") (pin "1") (pintype "passive"))
      (node (ref "U9") (pin "2") (pinfunction "VOUT_2") (pintype "passive"))
    )
    (net (code "204") (name "VCC3.3") (class "Default")
      (node (ref "C13") (pin "2") (pintype "passive"))
      (node (ref "C14") (pin "2") (pintype "passive"))
      (node (ref "C15") (pin "2") (pintype "passive"))
      (node (ref "C16") (pin "2") (pintype "passive"))
      (node (ref "C17") (pin "2") (pintype "passive"))
      (node (ref "C18") (pin "2") (pintype "passive"))
      (node (ref "C19") (pin "2") (pintype "passive"))
      (node (ref "C20") (pin "2") (pintype "passive"))
      (node (ref "C21") (pin "2") (pintype "passive"))
      (node (ref "C22") (pin "2") (pintype "passive"))
      (node (ref "C23") (pin "2") (pintype "passive"))
      (node (ref "C24") (pin "2") (pintype "passive"))
      (node (ref "C25") (pin "2") (pintype "passive"))
      (node (ref "C26") (pin "2") (pintype "passive"))
      (node (ref "C27") (pin "2") (pintype "passive"))
      (node (ref "C34") (pin "2") (pintype "passive"))
      (node (ref "C35") (pin "1") (pinfunction "VCC_1") (pintype "passive"))
      (node (ref "C36") (pin "1") (pintype "passive"))
      (node (ref "C38") (pin "1") (pintype "passive"))
      (node (ref "C39") (pin "1") (pintype "passive"))
      (node (ref "C42") (pin "2") (pintype "passive"))
      (node (ref "C43") (pin "2") (pintype "passive"))
      (node (ref "C44") (pin "2") (pintype "passive"))
      (node (ref "C45") (pin "2") (pintype "passive"))
      (node (ref "C46") (pin "2") (pintype "passive"))
      (node (ref "C47") (pin "2") (pintype "passive"))
      (node (ref "C48") (pin "2") (pintype "passive"))
      (node (ref "C49") (pin "1") (pintype "passive"))
      (node (ref "C51") (pin "1") (pintype "passive"))
      (node (ref "C52") (pin "1") (pintype "passive"))
      (node (ref "C69") (pin "2") (pintype "passive"))
      (node (ref "C71") (pin "2") (pintype "passive"))
      (node (ref "C81") (pin "2") (pintype "passive"))
      (node (ref "D1") (pin "1") (pintype "passive"))
      (node (ref "L2") (pin "2") (pintype "passive"))
      (node (ref "LCD1") (pin "24") (pinfunction "VDD3.3_24") (pintype "passive"))
      (node (ref "LCD1") (pin "25") (pinfunction "VDD3.3_25") (pintype "passive"))
      (node (ref "LED5") (pin "1") (pinfunction "1_1") (pintype "passive"))
      (node (ref "R10") (pin "2") (pintype "passive"))
      (node (ref "R11") (pin "2") (pintype "passive"))
      (node (ref "R13") (pin "2") (pintype "passive"))
      (node (ref "R15") (pin "2") (pintype "passive"))
      (node (ref "R16") (pin "2") (pintype "passive"))
      (node (ref "R17") (pin "2") (pintype "passive"))
      (node (ref "R18") (pin "2") (pintype "passive"))
      (node (ref "R19") (pin "2") (pintype "passive"))
      (node (ref "R2") (pin "1") (pintype "passive"))
      (node (ref "R20") (pin "2") (pintype "passive"))
      (node (ref "R21") (pin "2") (pintype "passive"))
      (node (ref "R22") (pin "1") (pintype "passive"))
      (node (ref "R36") (pin "1") (pintype "passive"))
      (node (ref "R37") (pin "2") (pintype "passive"))
      (node (ref "R38") (pin "2") (pintype "passive"))
      (node (ref "R39") (pin "2") (pintype "passive"))
      (node (ref "R4") (pin "2") (pintype "passive"))
      (node (ref "R40") (pin "2") (pintype "passive"))
      (node (ref "R5") (pin "2") (pintype "passive"))
      (node (ref "TF_CARD") (pin "4") (pinfunction "VDD_4") (pintype "passive"))
      (node (ref "U1") (pin "103") (pinfunction "VDD_103") (pintype "passive"))
      (node (ref "U1") (pin "114") (pinfunction "VDD_114") (pintype "passive"))
      (node (ref "U1") (pin "127") (pinfunction "VDD_127") (pintype "passive"))
      (node (ref "U1") (pin "136") (pinfunction "VDD_136") (pintype "passive"))
      (node (ref "U1") (pin "149") (pinfunction "VDD_149") (pintype "passive"))
      (node (ref "U1") (pin "15") (pinfunction "VDD_15") (pintype "passive"))
      (node (ref "U1") (pin "159") (pinfunction "VDD_159") (pintype "passive"))
      (node (ref "U1") (pin "172") (pinfunction "VDD_172") (pintype "passive"))
      (node (ref "U1") (pin "23") (pinfunction "VDD_23") (pintype "passive"))
      (node (ref "U1") (pin "36") (pinfunction "VDD_36") (pintype "passive"))
      (node (ref "U1") (pin "49") (pinfunction "VDD_49") (pintype "passive"))
      (node (ref "U1") (pin "62") (pinfunction "VDD_62") (pintype "passive"))
      (node (ref "U1") (pin "72") (pinfunction "VDD_72") (pintype "passive"))
      (node (ref "U1") (pin "82") (pinfunction "VDD_82") (pintype "passive"))
      (node (ref "U1") (pin "91") (pinfunction "VDD_91") (pintype "passive"))
      (node (ref "U11") (pin "1") (pinfunction "VDD0_1") (pintype "power_in"))
      (node (ref "U11") (pin "14") (pinfunction "VDD1_14") (pintype "power_in"))
      (node (ref "U11") (pin "27") (pinfunction "VDD2_27") (pintype "power_in"))
      (node (ref "U11") (pin "3") (pinfunction "VDDQ0_3") (pintype "power_in"))
      (node (ref "U11") (pin "43") (pinfunction "VDDQ2_43") (pintype "power_in"))
      (node (ref "U11") (pin "49") (pinfunction "VDDQ3_49") (pintype "power_in"))
      (node (ref "U11") (pin "9") (pinfunction "VDDQ1_9") (pintype "power_in"))
      (node (ref "U12") (pin "2") (pinfunction "OUT_2") (pintype "passive"))
      (node (ref "U12") (pin "4") (pinfunction "OUT_4") (pintype "passive"))
      (node (ref "U2") (pin "31") (pinfunction "AVDD_31") (pintype "passive"))
      (node (ref "U3") (pin "8") (pinfunction "VCC1_8") (pintype "passive"))
      (node (ref "U4") (pin "8") (pinfunction "VCC_8") (pintype "passive"))
      (node (ref "U6") (pin "1") (pinfunction "VCC_1") (pintype "passive"))
      (node (ref "U8") (pin "3") (pinfunction "VIN_3") (pintype "passive"))
      (node (ref "U9") (pin "3") (pinfunction "VIN_3") (pintype "passive"))
    )
    (net (code "205") (name "VCC5") (class "Default")
      (node (ref "C31") (pin "1") (pintype "passive"))
      (node (ref "C32") (pin "1") (pintype "passive"))
      (node (ref "C33") (pin "2") (pintype "passive"))
      (node (ref "C50") (pin "2") (pintype "passive"))
      (node (ref "J1") (pin "1") (pinfunction "1_1") (pintype "passive"))
      (node (ref "J1") (pin "2") (pinfunction "2_2") (pintype "passive"))
      (node (ref "LCD1") (pin "28") (pinfunction "BL_VDD_28") (pintype "passive"))
      (node (ref "POWER") (pin "1") (pinfunction "I/O_1") (pintype "passive"))
      (node (ref "R29") (pin "2") (pintype "passive"))
      (node (ref "U12") (pin "3") (pinfunction "IN_3") (pintype "passive"))
      (node (ref "U14") (pin "16") (pinfunction "VCC_16") (pintype "passive"))
    )
    (net (code "206") (name "unconnected-(J1-PadA)") (class "Default")
      (node (ref "J1") (pin "A") (pinfunction "A_A") (pintype "passive"))
    )
    (net (code "207") (name "unconnected-(J1-PadB)") (class "Default")
      (node (ref "J1") (pin "B") (pinfunction "B_B") (pintype "passive"))
    )
    (net (code "208") (name "unconnected-(LCD1-MO-Pad32)") (class "Default")
      (node (ref "LCD1") (pin "32") (pinfunction "MO_32") (pintype "passive"))
    )
    (net (code "209") (name "unconnected-(M1-NC-Pad27)") (class "Default")
      (node (ref "M1") (pin "27") (pinfunction "NC_27") (pintype "passive+no_connect"))
    )
    (net (code "210") (name "unconnected-(POWER-GND-Pad4)") (class "Default")
      (node (ref "POWER") (pin "4") (pinfunction "GND_4") (pintype "passive"))
    )
    (net (code "211") (name "unconnected-(POWER-GND-Pad5)") (class "Default")
      (node (ref "POWER") (pin "5") (pinfunction "GND_5") (pintype "passive"))
    )
    (net (code "212") (name "unconnected-(POWER-I{slash}O-Pad3)") (class "Default")
      (node (ref "POWER") (pin "3") (pinfunction "I/O_3") (pintype "passive"))
    )
    (net (code "213") (name "unconnected-(R30-Pad1)") (class "Default")
      (node (ref "R30") (pin "1") (pintype "passive"))
    )
    (net (code "214") (name "unconnected-(U2-CSB{slash}GPIO1-Pad15)") (class "Default")
      (node (ref "U2") (pin "15") (pinfunction "CSB/GPIO1_15") (pintype "passive"))
    )
    (net (code "215") (name "unconnected-(U2-OUT3-Pad22)") (class "Default")
      (node (ref "U2") (pin "22") (pinfunction "OUT3_22") (pintype "passive"))
    )
    (net (code "216") (name "unconnected-(U2-OUT4-Pad21)") (class "Default")
      (node (ref "U2") (pin "21") (pinfunction "OUT4_21") (pintype "passive"))
    )
    (net (code "217") (name "unconnected-(U14-CTS#-Pad9)") (class "Default")
      (node (ref "U14") (pin "9") (pinfunction "CTS#_9") (pintype "passive"))
    )
    (net (code "218") (name "unconnected-(U14-DCD#-Pad12)") (class "Default")
      (node (ref "U14") (pin "12") (pinfunction "DCD#_12") (pintype "passive"))
    )
    (net (code "219") (name "unconnected-(U14-DSR#-Pad10)") (class "Default")
      (node (ref "U14") (pin "10") (pinfunction "DSR#_10") (pintype "passive"))
    )
    (net (code "220") (name "unconnected-(U14-DTR#-Pad13)") (class "Default")
      (node (ref "U14") (pin "13") (pinfunction "DTR#_13") (pintype "passive"))
    )
    (net (code "221") (name "unconnected-(U14-R232-Pad15)") (class "Default")
      (node (ref "U14") (pin "15") (pinfunction "R232_15") (pintype "passive"))
    )
    (net (code "222") (name "unconnected-(U14-RI#-Pad11)") (class "Default")
      (node (ref "U14") (pin "11") (pinfunction "RI#_11") (pintype "passive"))
    )
    (net (code "223") (name "unconnected-(U14-RTS#-Pad14)") (class "Default")
      (node (ref "U14") (pin "14") (pinfunction "RTS#_14") (pintype "passive"))
    )
    (net (code "224") (name "unconnected-(USB_232-NC-Pad4)") (class "Default")
      (node (ref "USB_232") (pin "4") (pinfunction "NC_4") (pintype "passive"))
    )
    (net (code "225") (name "unconnected-(USB_SLAVE-NC-Pad4)") (class "Default")
      (node (ref "USB_SLAVE") (pin "4") (pinfunction "NC_4") (pintype "passive"))
    )
    (net (code "226") (name "unconnected-(Y5-NC-Pad1)") (class "Default")
      (node (ref "Y5") (pin "1") (pinfunction "NC_1") (pintype "passive"))
    )
  )
)
